# AMR3350-V4.net
KiCad netlist of a schematic drawn in EAGLE
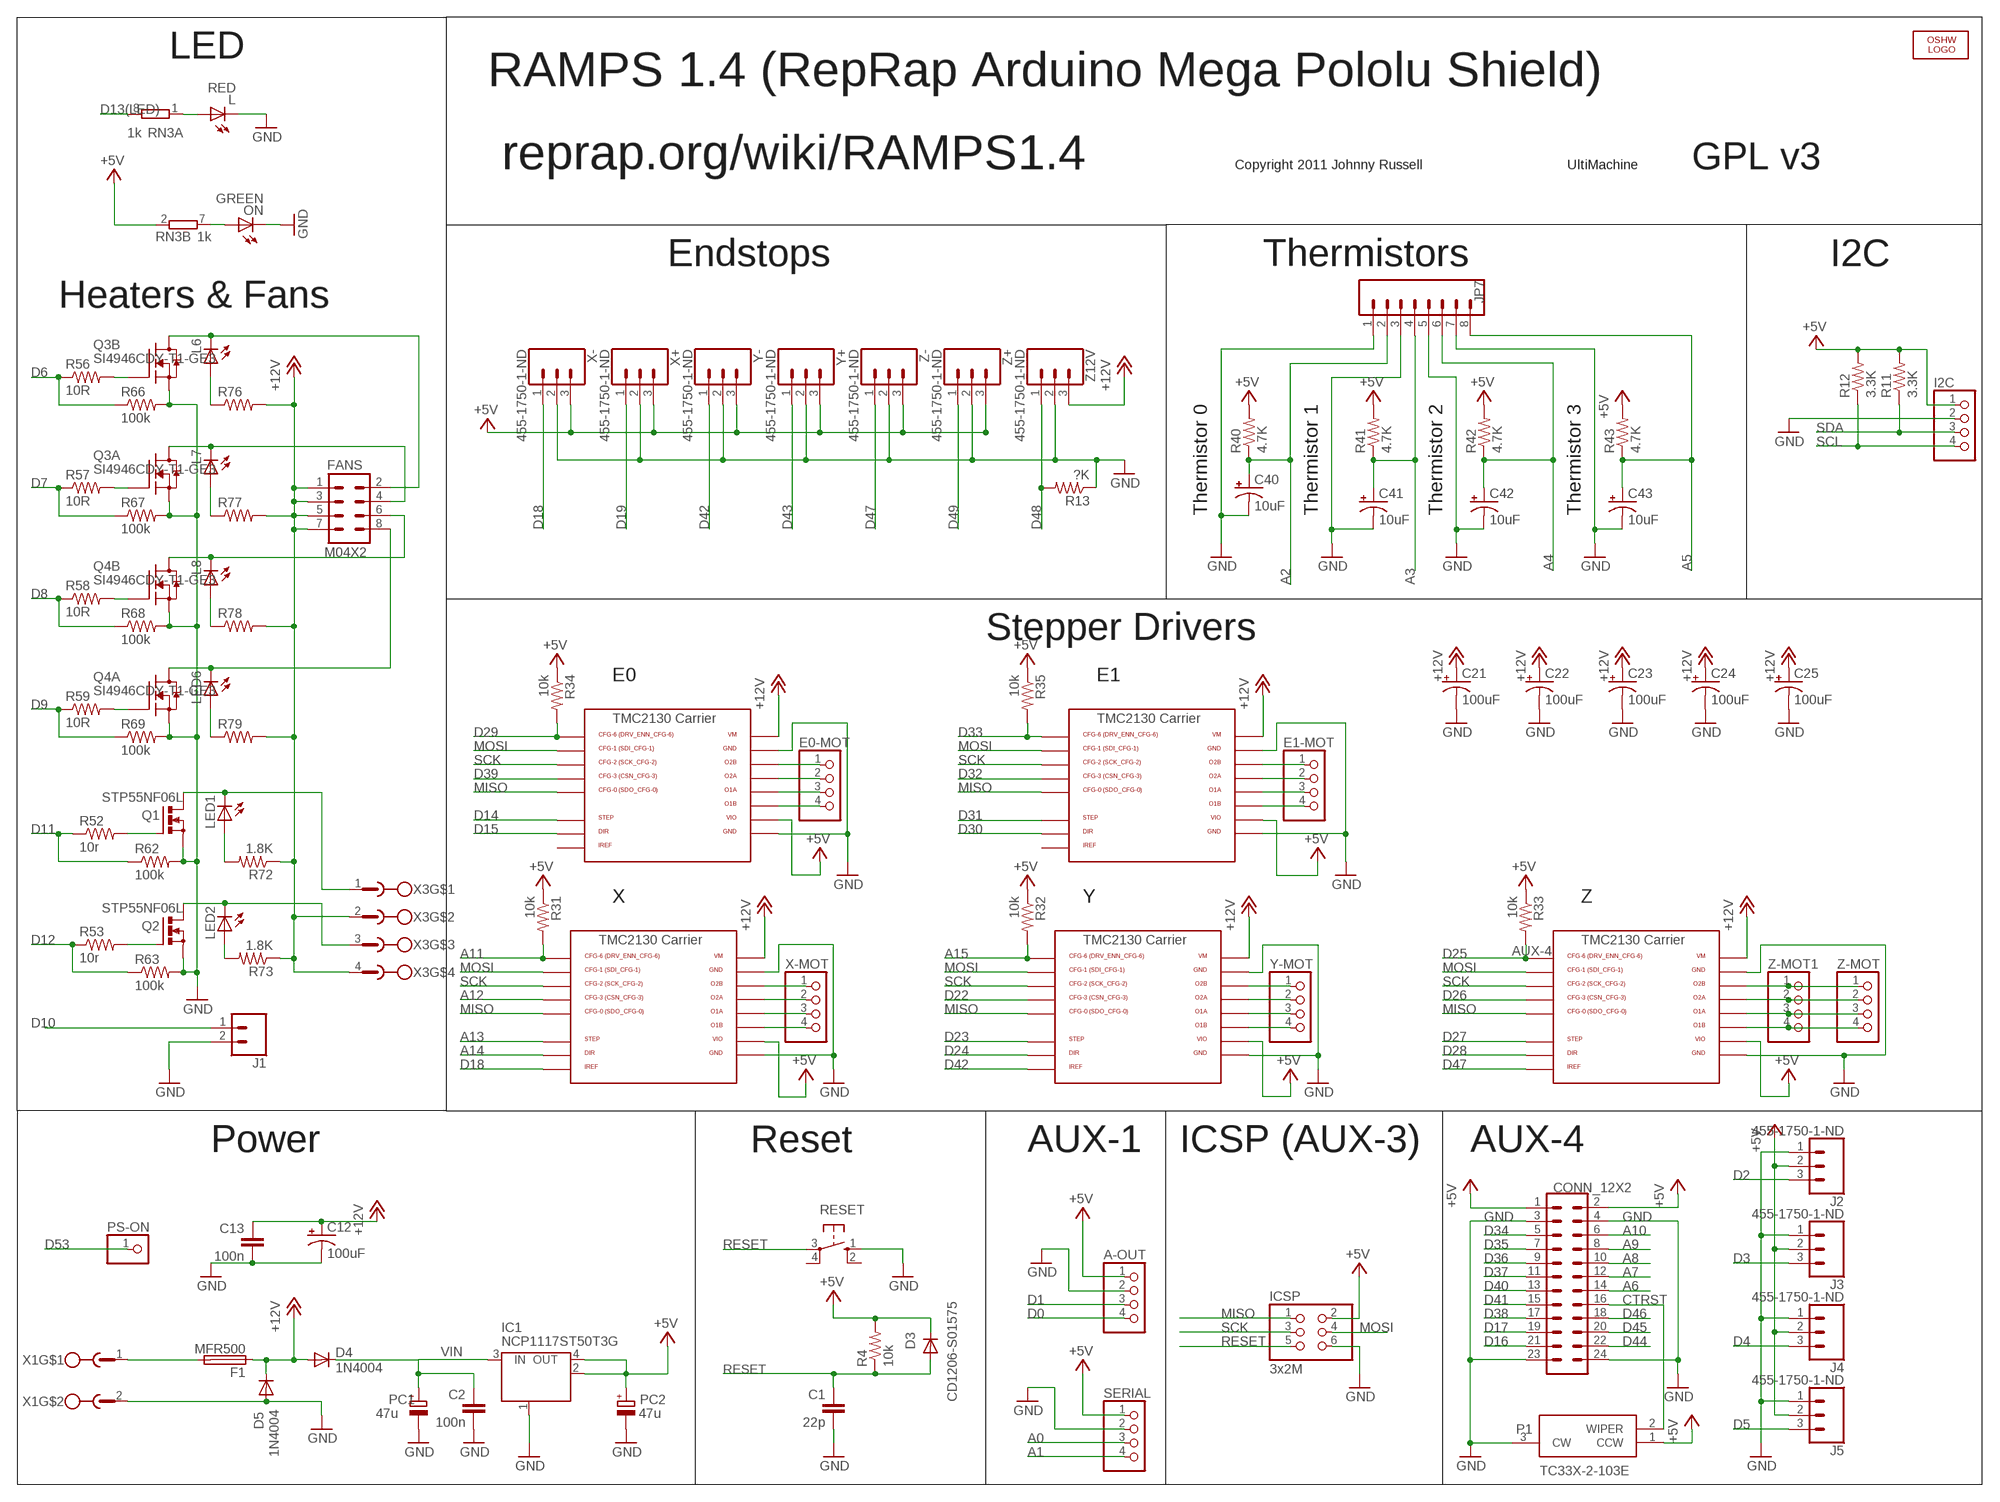
[diagram p0: schematic, sheet 1, part 1 of 2]
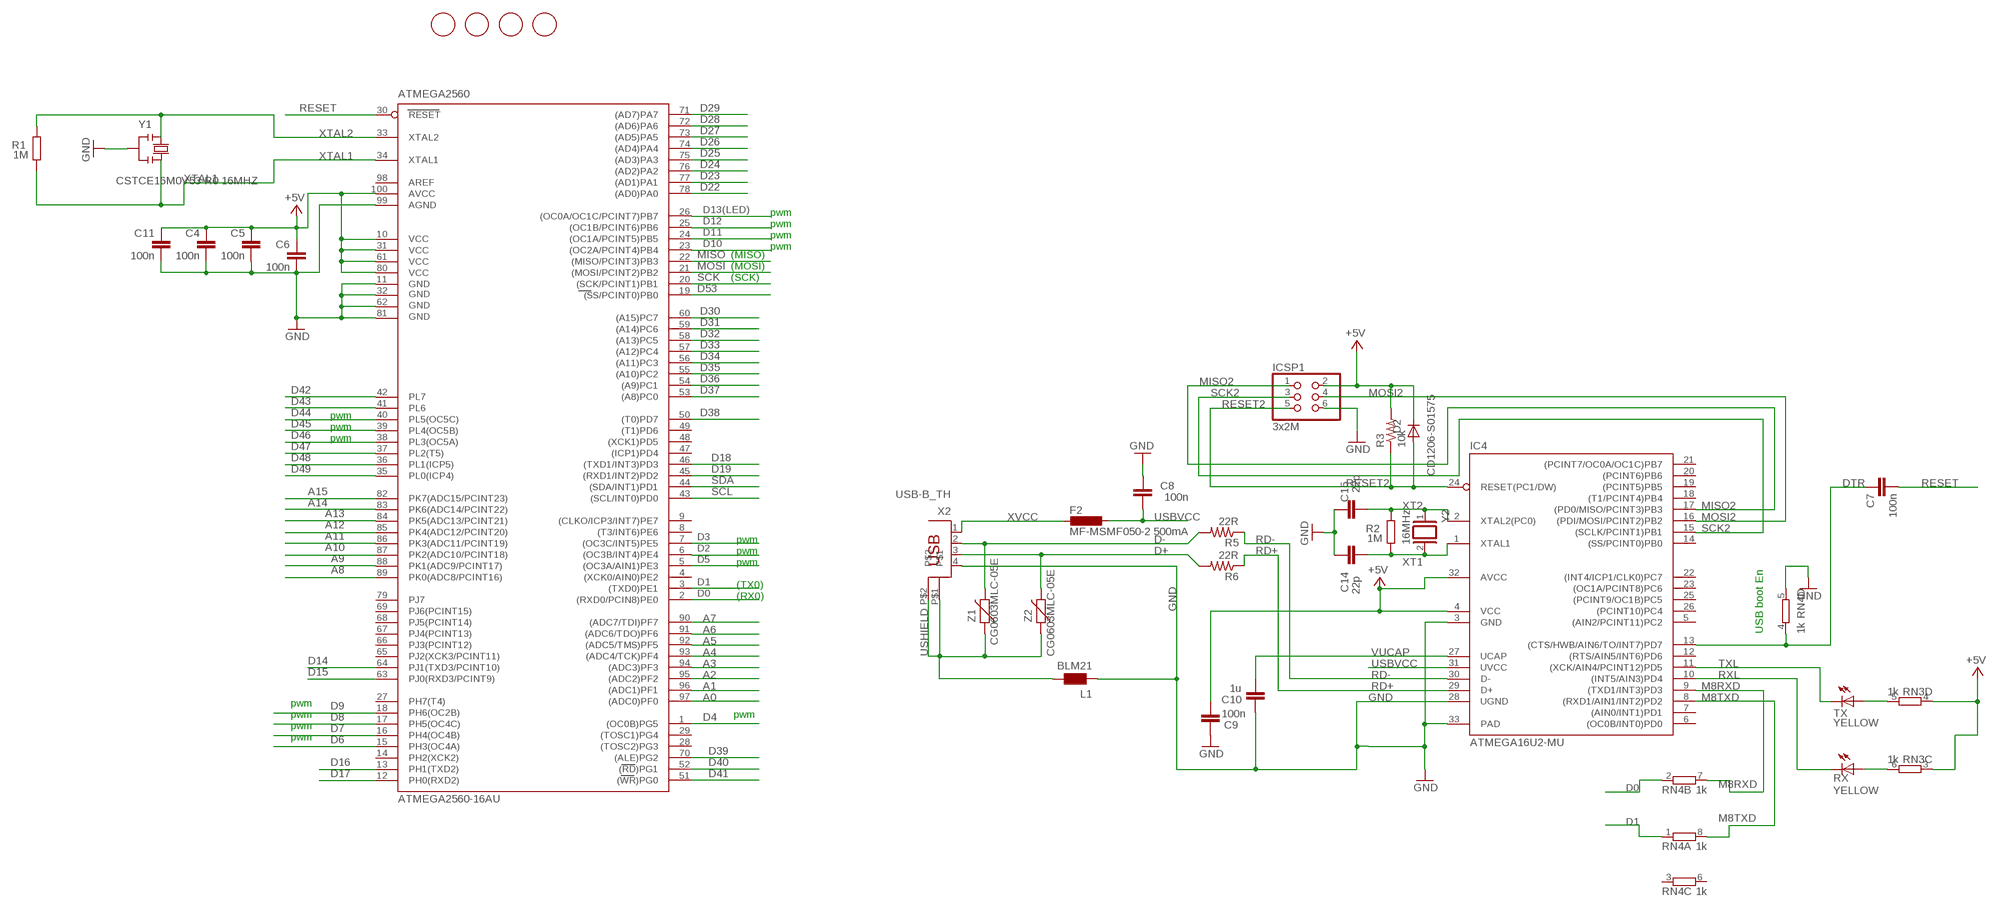
[diagram p1: schematic, sheet 1, part 2 of 2]

(export (version "E")
  (design (tool "Eeschema 10.0.6"))
  (components
    (comp (ref "A-OUT")
      (value "PINHD-1X4")
      (footprint "eagle-import:1X04")
      (libsource (lib "eagle-import") (part "PINHD-1X4"))
    )
    (comp (ref "ATMEGA2560")
      (value "ATMEGA2560-16AU")
      (footprint "eagle-import:TQFP100")
      (libsource (lib "eagle-import") (part "ATMEGA2560AU2560-16"))
    )
    (comp (ref "AUX-4")
      (value "CONN_12X2")
      (footprint "eagle-import:2X12")
      (libsource (lib "eagle-import") (part "CONN_12X2"))
    )
    (comp (ref "C1")
      (value "22p")
      (footprint "eagle-import:C0603-ROUND")
      (libsource (lib "eagle-import") (part "C-EU0603-RND"))
    )
    (comp (ref "C2")
      (value "100n")
      (footprint "eagle-import:C0805RND")
      (libsource (lib "eagle-import") (part "C-EU"))
    )
    (comp (ref "C4")
      (value "100n")
      (footprint "eagle-import:C0805RND")
      (libsource (lib "eagle-import") (part "C-EU"))
    )
    (comp (ref "C5")
      (value "100n")
      (footprint "eagle-import:C0603-ROUND")
      (libsource (lib "eagle-import") (part "C-EU0603-RND"))
    )
    (comp (ref "C6")
      (value "100n")
      (footprint "eagle-import:C0603-ROUND")
      (libsource (lib "eagle-import") (part "C-EU0603-RND"))
    )
    (comp (ref "C7")
      (value "100n")
      (footprint "eagle-import:C0603-ROUND")
      (libsource (lib "eagle-import") (part "C-EU0603-RND"))
    )
    (comp (ref "C8")
      (value "100n")
      (footprint "eagle-import:C0603-ROUND")
      (libsource (lib "eagle-import") (part "C-EU0603-RND"))
    )
    (comp (ref "C9")
      (value "100n")
      (footprint "eagle-import:C0603-ROUND")
      (libsource (lib "eagle-import") (part "C-EU0603-RND"))
    )
    (comp (ref "C10")
      (value "1u")
      (footprint "eagle-import:C0603-ROUND")
      (libsource (lib "eagle-import") (part "C-EU0603-RND"))
    )
    (comp (ref "C11")
      (value "100n")
      (footprint "eagle-import:C0603-ROUND")
      (libsource (lib "eagle-import") (part "C-EU0603-RND"))
    )
    (comp (ref "C12")
      (value "100uF")
      (footprint "eagle-import:153CLV-0605")
      (libsource (lib "eagle-import") (part "CPOL-US153CLV-0605"))
    )
    (comp (ref "C13")
      (value "100n")
      (footprint "eagle-import:C0603-ROUND")
      (libsource (lib "eagle-import") (part "C-EU0603-RND"))
    )
    (comp (ref "C14")
      (value "22p")
      (footprint "eagle-import:C0603-ROUND")
      (libsource (lib "eagle-import") (part "C-EU0603-RND"))
    )
    (comp (ref "C15")
      (value "22p")
      (footprint "eagle-import:C0603-ROUND")
      (libsource (lib "eagle-import") (part "C-EU0603-RND"))
    )
    (comp (ref "C21")
      (value "100uF")
      (footprint "eagle-import:153CLV-0605")
      (libsource (lib "eagle-import") (part "CPOL-US153CLV-0605"))
    )
    (comp (ref "C22")
      (value "100uF")
      (footprint "eagle-import:153CLV-0605")
      (libsource (lib "eagle-import") (part "CPOL-US153CLV-0605"))
    )
    (comp (ref "C23")
      (value "100uF")
      (footprint "eagle-import:153CLV-0605")
      (libsource (lib "eagle-import") (part "CPOL-US153CLV-0605"))
    )
    (comp (ref "C24")
      (value "100uF")
      (footprint "eagle-import:153CLV-0605")
      (libsource (lib "eagle-import") (part "CPOL-US153CLV-0605"))
    )
    (comp (ref "C25")
      (value "100uF")
      (footprint "eagle-import:153CLV-0605")
      (libsource (lib "eagle-import") (part "CPOL-US153CLV-0605"))
    )
    (comp (ref "C40")
      (value "10uF")
      (footprint "eagle-import:153CLV-0405")
      (libsource (lib "eagle-import") (part "CPOL-US153CLV-0405"))
    )
    (comp (ref "C41")
      (value "10uF")
      (footprint "eagle-import:153CLV-0405")
      (libsource (lib "eagle-import") (part "CPOL-US153CLV-0405"))
    )
    (comp (ref "C42")
      (value "10uF")
      (footprint "eagle-import:153CLV-0405")
      (libsource (lib "eagle-import") (part "CPOL-US153CLV-0405"))
    )
    (comp (ref "C43")
      (value "10uF")
      (footprint "eagle-import:153CLV-0405")
      (libsource (lib "eagle-import") (part "CPOL-US153CLV-0405"))
    )
    (comp (ref "D2")
      (value "CD1206-S01575")
      (footprint "eagle-import:MINIMELF")
      (libsource (lib "eagle-import") (part "DIODE-MINIMELF"))
    )
    (comp (ref "D3")
      (value "CD1206-S01575")
      (footprint "eagle-import:MINIMELF")
      (libsource (lib "eagle-import") (part "DIODE-MINIMELF"))
    )
    (comp (ref "D4")
      (value "1N4004")
      (footprint "eagle-import:DO41-10")
      (libsource (lib "eagle-import") (part "1N4004"))
    )
    (comp (ref "D5")
      (value "1N4004")
      (footprint "eagle-import:DO41-10")
      (libsource (lib "eagle-import") (part "1N4004"))
    )
    (comp (ref "E0-MOT")
      (value "PINHD-1X4")
      (footprint "eagle-import:1X04")
      (libsource (lib "eagle-import") (part "PINHD-1X4"))
    )
    (comp (ref "E1-MOT")
      (value "PINHD-1X4")
      (footprint "eagle-import:1X04")
      (libsource (lib "eagle-import") (part "PINHD-1X4"))
    )
    (comp (ref "F1")
      (value "MFR500")
      (footprint "eagle-import:MFR500")
      (libsource (lib "eagle-import") (part "PTCFUSE"))
    )
    (comp (ref "F2")
      (value "MF-MSMF050-2 500mA")
      (footprint "eagle-import:L1812")
      (libsource (lib "eagle-import") (part "L-EUL1812"))
    )
    (comp (ref "FANS")
      (value "M04X2")
      (footprint "eagle-import:2X4")
      (libsource (lib "eagle-import") (part "M04X2"))
    )
    (comp (ref "FD1")
      (value "FIDUCIALMOUNT")
      (footprint "eagle-import:FIDUCIA-MOUNT")
      (libsource (lib "eagle-import") (part "FIDUCIALMOUNT"))
    )
    (comp (ref "FD2")
      (value "FIDUCIALMOUNT")
      (footprint "eagle-import:FIDUCIA-MOUNT")
      (libsource (lib "eagle-import") (part "FIDUCIALMOUNT"))
    )
    (comp (ref "FD3")
      (value "FIDUCIALMOUNT")
      (footprint "eagle-import:FIDUCIA-MOUNT")
      (libsource (lib "eagle-import") (part "FIDUCIALMOUNT"))
    )
    (comp (ref "FD4")
      (value "FIDUCIALMOUNT")
      (footprint "eagle-import:FIDUCIA-MOUNT")
      (libsource (lib "eagle-import") (part "FIDUCIALMOUNT"))
    )
    (comp (ref "I2C")
      (value "PINHD-1X4")
      (footprint "eagle-import:1X04")
      (libsource (lib "eagle-import") (part "PINHD-1X4"))
    )
    (comp (ref "IC1")
      (value "NCP1117ST50T3G")
      (footprint "eagle-import:SOT223")
      (libsource (lib "eagle-import") (part "MC33269ST-3.3T3"))
    )
    (comp (ref "IC4")
      (value "ATMEGA16U2-MU")
      (footprint "eagle-import:MLF32")
      (libsource (lib "eagle-import") (part "ATMEGA16U2-MU"))
    )
    (comp (ref "ICSP")
      (value "3x2M")
      (footprint "eagle-import:2X03")
      (libsource (lib "eagle-import") (part "PINHD-2X3"))
    )
    (comp (ref "ICSP1")
      (value "3x2M")
      (footprint "eagle-import:2X03")
      (libsource (lib "eagle-import") (part "PINHD-2X3"))
    )
    (comp (ref "J1")
      (value "CONN_02")
      (footprint "eagle-import:1X02")
      (libsource (lib "eagle-import") (part "CONN_02"))
    )
    (comp (ref "J2")
      (value "455-1750-1-ND")
      (footprint "eagle-import:1X03")
      (libsource (lib "eagle-import") (part "CONN_03"))
    )
    (comp (ref "J3")
      (value "455-1750-1-ND")
      (footprint "eagle-import:1X03")
      (libsource (lib "eagle-import") (part "CONN_03"))
    )
    (comp (ref "J4")
      (value "455-1750-1-ND")
      (footprint "eagle-import:1X03")
      (libsource (lib "eagle-import") (part "CONN_03"))
    )
    (comp (ref "J5")
      (value "455-1750-1-ND")
      (footprint "eagle-import:1X03")
      (libsource (lib "eagle-import") (part "CONN_03"))
    )
    (comp (ref "JP7")
      (value "CONN_08\"")
      (footprint "eagle-import:1X08")
      (libsource (lib "eagle-import") (part "CONN_08{dblquote}"))
    )
    (comp (ref "L")
      (value "RED")
      (footprint "eagle-import:CHIP-LED0805")
      (libsource (lib "eagle-import") (part "LEDCHIP-LED0805"))
    )
    (comp (ref "L1")
      (value "BLM21")
      (footprint "eagle-import:0805")
      (libsource (lib "eagle-import") (part "WE-CBF_0805"))
    )
    (comp (ref "L6")
      (value "LEDCHIP-LED0603")
      (footprint "eagle-import:CHIP-LED0603")
      (libsource (lib "eagle-import") (part "LEDCHIP-LED0603"))
    )
    (comp (ref "L7")
      (value "LEDCHIP-LED0603")
      (footprint "eagle-import:CHIP-LED0603")
      (libsource (lib "eagle-import") (part "LEDCHIP-LED0603"))
    )
    (comp (ref "L8")
      (value "LEDCHIP-LED0603")
      (footprint "eagle-import:CHIP-LED0603")
      (libsource (lib "eagle-import") (part "LEDCHIP-LED0603"))
    )
    (comp (ref "LED1")
      (value "LEDCHIP-LED0805")
      (footprint "eagle-import:CHIP-LED0805")
      (libsource (lib "eagle-import") (part "LEDCHIP-LED0805"))
    )
    (comp (ref "LED2")
      (value "LEDCHIP-LED0805")
      (footprint "eagle-import:CHIP-LED0805")
      (libsource (lib "eagle-import") (part "LEDCHIP-LED0805"))
    )
    (comp (ref "LED6")
      (value "LEDCHIP-LED0603")
      (footprint "eagle-import:CHIP-LED0603")
      (libsource (lib "eagle-import") (part "LEDCHIP-LED0603"))
    )
    (comp (ref "LOGO2")
      (value "OSHW_LOGO_6MILX0100-NT")
      (footprint "eagle-import:OSHW_6X100_NOTEXT")
      (libsource (lib "eagle-import") (part "OSHW_LOGO_6MILX0100-NT"))
    )
    (comp (ref "ON")
      (value "GREEN")
      (footprint "eagle-import:CHIP-LED0805")
      (libsource (lib "eagle-import") (part "LEDCHIP-LED0805"))
    )
    (comp (ref "P1")
      (value "TC33X-2-103E")
      (footprint "eagle-import:TC33X-2_1")
      (fields (field (name "RS_PART_NUMBER") "1673549"))
      (libsource (lib "eagle-import") (part "TC33X-2-103E"))
    )
    (comp (ref "PC1")
      (value "47u")
      (footprint "eagle-import:PANASONIC_D")
      (libsource (lib "eagle-import") (part "CPOL-EUD"))
    )
    (comp (ref "PC2")
      (value "47u")
      (footprint "eagle-import:PANASONIC_D")
      (libsource (lib "eagle-import") (part "CPOL-EUD"))
    )
    (comp (ref "PS-ON")
      (value "PINHD-1X1")
      (footprint "eagle-import:1X01")
      (libsource (lib "eagle-import") (part "PINHD-1X1"))
    )
    (comp (ref "Q1")
      (value "STP55NF06L")
      (footprint "eagle-import:TO220BV")
      (libsource (lib "eagle-import") (part "IRF512"))
    )
    (comp (ref "Q2")
      (value "STP55NF06L")
      (footprint "eagle-import:TO220BV")
      (libsource (lib "eagle-import") (part "IRF512"))
    )
    (comp (ref "Q3")
      (value "SI4946CDY-T1-GE3")
      (footprint "eagle-import:SOIC127P600X175-8N")
      (libsource (lib "eagle-import") (part "SI4946CDY-T1-GE3"))
    )
    (comp (ref "Q4")
      (value "SI4946CDY-T1-GE3")
      (footprint "eagle-import:SOIC127P600X175-8N")
      (libsource (lib "eagle-import") (part "SI4946CDY-T1-GE3"))
    )
    (comp (ref "R1")
      (value "1M")
      (footprint "eagle-import:R0603-ROUND")
      (libsource (lib "eagle-import") (part "R-EU_R0603"))
    )
    (comp (ref "R2")
      (value "1M")
      (footprint "eagle-import:R0603-ROUND")
      (libsource (lib "eagle-import") (part "R-EU_R0603"))
    )
    (comp (ref "R3")
      (value "10k")
      (footprint "eagle-import:R0603")
      (libsource (lib "eagle-import") (part "resistor_348_R-US_R0603"))
    )
    (comp (ref "R4")
      (value "10k")
      (footprint "eagle-import:R0603")
      (libsource (lib "eagle-import") (part "resistor_348_R-US_R0603"))
    )
    (comp (ref "R5")
      (value "22R")
      (footprint "eagle-import:R0603")
      (libsource (lib "eagle-import") (part "resistor_348_R-US_R0603"))
    )
    (comp (ref "R6")
      (value "22R")
      (footprint "eagle-import:R0603")
      (libsource (lib "eagle-import") (part "resistor_348_R-US_R0603"))
    )
    (comp (ref "R11")
      (value "3.3K")
      (footprint "eagle-import:R0603")
      (libsource (lib "eagle-import") (part "R-US_R0603"))
    )
    (comp (ref "R12")
      (value "3.3K")
      (footprint "eagle-import:R0603")
      (libsource (lib "eagle-import") (part "R-US_R0603"))
    )
    (comp (ref "R13")
      (value "?K")
      (footprint "eagle-import:R0805")
      (libsource (lib "eagle-import") (part "R-US_R0805"))
    )
    (comp (ref "R31")
      (value "10k")
      (footprint "eagle-import:R0805")
      (libsource (lib "eagle-import") (part "R-US_R0805"))
    )
    (comp (ref "R32")
      (value "10k")
      (footprint "eagle-import:R0805")
      (libsource (lib "eagle-import") (part "R-US_R0805"))
    )
    (comp (ref "R33")
      (value "10k")
      (footprint "eagle-import:R0805")
      (libsource (lib "eagle-import") (part "R-US_R0805"))
    )
    (comp (ref "R34")
      (value "10k")
      (footprint "eagle-import:R0805")
      (libsource (lib "eagle-import") (part "R-US_R0805"))
    )
    (comp (ref "R35")
      (value "10k")
      (footprint "eagle-import:R0805")
      (libsource (lib "eagle-import") (part "R-US_R0805"))
    )
    (comp (ref "R40")
      (value "4.7K")
      (footprint "eagle-import:R0805")
      (libsource (lib "eagle-import") (part "R-US_R0805"))
    )
    (comp (ref "R41")
      (value "4.7K")
      (footprint "eagle-import:R0805")
      (libsource (lib "eagle-import") (part "R-US_R0805"))
    )
    (comp (ref "R42")
      (value "4.7K")
      (footprint "eagle-import:R0805")
      (libsource (lib "eagle-import") (part "R-US_R0805"))
    )
    (comp (ref "R43")
      (value "4.7K")
      (footprint "eagle-import:R0805")
      (libsource (lib "eagle-import") (part "R-US_R0805"))
    )
    (comp (ref "R52")
      (value "10r")
      (footprint "eagle-import:R0805")
      (libsource (lib "eagle-import") (part "resistor_R-US_R0805"))
    )
    (comp (ref "R53")
      (value "10r")
      (footprint "eagle-import:M0805")
      (libsource (lib "eagle-import") (part "resistor_R-US_M0805"))
    )
    (comp (ref "R56")
      (value "10R")
      (footprint "eagle-import:R0603")
      (libsource (lib "eagle-import") (part "resistor_348_R-US_R0603"))
    )
    (comp (ref "R57")
      (value "10R")
      (footprint "eagle-import:R0603")
      (libsource (lib "eagle-import") (part "resistor_348_R-US_R0603"))
    )
    (comp (ref "R58")
      (value "10R")
      (footprint "eagle-import:R0603")
      (libsource (lib "eagle-import") (part "resistor_348_R-US_R0603"))
    )
    (comp (ref "R59")
      (value "10R")
      (footprint "eagle-import:R0603")
      (libsource (lib "eagle-import") (part "resistor_348_R-US_R0603"))
    )
    (comp (ref "R62")
      (value "100k")
      (footprint "eagle-import:R0805")
      (libsource (lib "eagle-import") (part "R-US_R0805"))
    )
    (comp (ref "R63")
      (value "100k")
      (footprint "eagle-import:R0805")
      (libsource (lib "eagle-import") (part "R-US_R0805"))
    )
    (comp (ref "R66")
      (value "100k")
      (footprint "eagle-import:R0603")
      (libsource (lib "eagle-import") (part "resistor_348_R-US_R0603"))
    )
    (comp (ref "R67")
      (value "100k")
      (footprint "eagle-import:R0603")
      (libsource (lib "eagle-import") (part "resistor_348_R-US_R0603"))
    )
    (comp (ref "R68")
      (value "100k")
      (footprint "eagle-import:R0603")
      (libsource (lib "eagle-import") (part "resistor_348_R-US_R0603"))
    )
    (comp (ref "R69")
      (value "100k")
      (footprint "eagle-import:R0603")
      (libsource (lib "eagle-import") (part "resistor_348_R-US_R0603"))
    )
    (comp (ref "R72")
      (value "1.8K")
      (footprint "eagle-import:R0805")
      (libsource (lib "eagle-import") (part "R-US_R0805"))
    )
    (comp (ref "R73")
      (value "1.8K")
      (footprint "eagle-import:R0805")
      (libsource (lib "eagle-import") (part "R-US_R0805"))
    )
    (comp (ref "R76")
      (value "R-US_R0603")
      (footprint "eagle-import:R0603")
      (libsource (lib "eagle-import") (part "resistor_348_R-US_R0603"))
    )
    (comp (ref "R77")
      (value "R-US_R0603")
      (footprint "eagle-import:R0603")
      (libsource (lib "eagle-import") (part "resistor_348_R-US_R0603"))
    )
    (comp (ref "R78")
      (value "R-US_R0603")
      (footprint "eagle-import:R0603")
      (libsource (lib "eagle-import") (part "resistor_348_R-US_R0603"))
    )
    (comp (ref "R79")
      (value "R-US_R0603")
      (footprint "eagle-import:R0603")
      (libsource (lib "eagle-import") (part "resistor_348_R-US_R0603"))
    )
    (comp (ref "RESET")
      (value "10-XX")
      (footprint "eagle-import:B3F-10XX")
      (fields (field (name "MPN") "B3F-1000"))
      (libsource (lib "eagle-import") (part "10-XX"))
    )
    (comp (ref "RN3")
      (value "1k")
      (footprint "eagle-import:CAY16")
      (libsource (lib "eagle-import") (part "4R-NCAY16"))
    )
    (comp (ref "RN4")
      (value "1k")
      (footprint "eagle-import:CAY16")
      (libsource (lib "eagle-import") (part "4R-NCAY16"))
    )
    (comp (ref "RX")
      (value "YELLOW")
      (footprint "eagle-import:CHIP-LED0805")
      (libsource (lib "eagle-import") (part "LEDCHIP-LED0805"))
    )
    (comp (ref "SERIAL")
      (value "PINHD-1X4")
      (footprint "eagle-import:1X04")
      (libsource (lib "eagle-import") (part "PINHD-1X4"))
    )
    (comp (ref "TX")
      (value "YELLOW")
      (footprint "eagle-import:CHIP-LED0805")
      (libsource (lib "eagle-import") (part "LEDCHIP-LED0805"))
    )
    (comp (ref "U$1")
      (value "TMC2130BREAKOUT")
      (footprint "eagle-import:TMC2130BREAKOUT")
      (libsource (lib "eagle-import") (part "TMC2130BREAKOUT"))
    )
    (comp (ref "U$2")
      (value "TMC2130BREAKOUT")
      (footprint "eagle-import:TMC2130BREAKOUT")
      (libsource (lib "eagle-import") (part "TMC2130BREAKOUT"))
    )
    (comp (ref "U$3")
      (value "TMC2130BREAKOUT")
      (footprint "eagle-import:TMC2130BREAKOUT")
      (libsource (lib "eagle-import") (part "TMC2130BREAKOUT"))
    )
    (comp (ref "U$4")
      (value "TMC2130BREAKOUT")
      (footprint "eagle-import:TMC2130BREAKOUT")
      (libsource (lib "eagle-import") (part "TMC2130BREAKOUT"))
    )
    (comp (ref "U$5")
      (value "TMC2130BREAKOUT")
      (footprint "eagle-import:TMC2130BREAKOUT")
      (libsource (lib "eagle-import") (part "TMC2130BREAKOUT"))
    )
    (comp (ref "X+")
      (value "455-1750-1-ND")
      (footprint "eagle-import:1X03")
      (libsource (lib "eagle-import") (part "CONN_03"))
    )
    (comp (ref "X-")
      (value "455-1750-1-ND")
      (footprint "eagle-import:1X03")
      (libsource (lib "eagle-import") (part "CONN_03"))
    )
    (comp (ref "X-MOT")
      (value "PINHD-1X4")
      (footprint "eagle-import:1X04")
      (libsource (lib "eagle-import") (part "PINHD-1X4"))
    )
    (comp (ref "X1")
      (value "2-PIN")
      (footprint "eagle-import:2-PIN")
      (libsource (lib "eagle-import") (part "2-PIN"))
    )
    (comp (ref "X2")
      (value "USB-B_TH")
      (footprint "eagle-import:PN61729-NOSILK")
      (libsource (lib "eagle-import") (part "PN61729NOSILK"))
    )
    (comp (ref "X3")
      (value "4-PIN")
      (footprint "eagle-import:4-PIN")
      (libsource (lib "eagle-import") (part "4-PIN"))
    )
    (comp (ref "Y+")
      (value "455-1750-1-ND")
      (footprint "eagle-import:1X03")
      (libsource (lib "eagle-import") (part "CONN_03"))
    )
    (comp (ref "Y-")
      (value "455-1750-1-ND")
      (footprint "eagle-import:1X03")
      (libsource (lib "eagle-import") (part "CONN_03"))
    )
    (comp (ref "Y-MOT")
      (value "PINHD-1X4")
      (footprint "eagle-import:1X04")
      (libsource (lib "eagle-import") (part "PINHD-1X4"))
    )
    (comp (ref "Y1")
      (value "CSTCE16M0V53-R0 16MHZ")
      (footprint "eagle-import:RESONATOR")
      (libsource (lib "eagle-import") (part "RESONATORMU"))
    )
    (comp (ref "Y2")
      (value "16MHz")
      (footprint "eagle-import:QS")
      (libsource (lib "eagle-import") (part "XTAL/S"))
    )
    (comp (ref "Z+")
      (value "455-1750-1-ND")
      (footprint "eagle-import:1X03")
      (libsource (lib "eagle-import") (part "CONN_03"))
    )
    (comp (ref "Z-")
      (value "455-1750-1-ND")
      (footprint "eagle-import:1X03")
      (libsource (lib "eagle-import") (part "CONN_03"))
    )
    (comp (ref "Z-MOT")
      (value "PINHD-1X4")
      (footprint "eagle-import:1X04")
      (libsource (lib "eagle-import") (part "PINHD-1X4"))
    )
    (comp (ref "Z-MOT1")
      (value "PINHD-1X4")
      (footprint "eagle-import:1X04")
      (libsource (lib "eagle-import") (part "PINHD-1X4"))
    )
    (comp (ref "Z1")
      (value "CG0603MLC-05E")
      (footprint "eagle-import:CT_CN0603")
      (libsource (lib "eagle-import") (part "VARISTORCN0603"))
    )
    (comp (ref "Z2")
      (value "CG0603MLC-05E")
      (footprint "eagle-import:CT_CN0603")
      (libsource (lib "eagle-import") (part "VARISTORCN0603"))
    )
    (comp (ref "Z12V")
      (value "455-1750-1-ND")
      (footprint "eagle-import:1X03")
      (libsource (lib "eagle-import") (part "CONN_03"))
    )
  )
  (nets
    (net (code "1") (name "+5V") (class "Default")
      (node (ref "A-OUT") (pin "1") (pinfunction "1_1") (pintype "passive"))
      (node (ref "ATMEGA2560") (pin "10") (pinfunction "VCC_10") (pintype "power_in"))
      (node (ref "ATMEGA2560") (pin "100") (pinfunction "AVCC_100") (pintype "power_in"))
      (node (ref "ATMEGA2560") (pin "31") (pinfunction "VCC1_31") (pintype "power_in"))
      (node (ref "ATMEGA2560") (pin "61") (pinfunction "VCC2_61") (pintype "power_in"))
      (node (ref "ATMEGA2560") (pin "80") (pinfunction "VCC3_80") (pintype "power_in"))
      (node (ref "AUX-4") (pin "1") (pinfunction "1_1") (pintype "passive"))
      (node (ref "AUX-4") (pin "2") (pinfunction "2_2") (pintype "passive"))
      (node (ref "C11") (pin "1") (pinfunction "1_1") (pintype "passive"))
      (node (ref "C4") (pin "1") (pinfunction "1_1") (pintype "passive"))
      (node (ref "C5") (pin "1") (pinfunction "1_1") (pintype "passive"))
      (node (ref "C6") (pin "1") (pinfunction "1_1") (pintype "passive"))
      (node (ref "C9") (pin "1") (pinfunction "1_1") (pintype "passive"))
      (node (ref "D2") (pin "C") (pinfunction "C_C") (pintype "passive"))
      (node (ref "D3") (pin "C") (pinfunction "C_C") (pintype "passive"))
      (node (ref "I2C") (pin "1") (pinfunction "1_1") (pintype "passive"))
      (node (ref "IC1") (pin "2") (pinfunction "OUT_2") (pintype "passive"))
      (node (ref "IC1") (pin "4") (pinfunction "OUT_4") (pintype "passive"))
      (node (ref "IC4") (pin "32") (pinfunction "AVCC_32") (pintype "power_in"))
      (node (ref "IC4") (pin "4") (pinfunction "VCC_4") (pintype "power_in"))
      (node (ref "ICSP") (pin "2") (pinfunction "2_2") (pintype "passive"))
      (node (ref "ICSP1") (pin "2") (pinfunction "2_2") (pintype "passive"))
      (node (ref "J2") (pin "2") (pinfunction "2_2") (pintype "passive"))
      (node (ref "J3") (pin "2") (pinfunction "2_2") (pintype "passive"))
      (node (ref "J4") (pin "2") (pinfunction "2_2") (pintype "passive"))
      (node (ref "J5") (pin "2") (pinfunction "2_2") (pintype "passive"))
      (node (ref "P1") (pin "1") (pinfunction "CCW_1") (pintype "bidirectional"))
      (node (ref "PC2") (pin "+") (pinfunction "+_+") (pintype "passive"))
      (node (ref "R11") (pin "2") (pinfunction "2_2") (pintype "passive"))
      (node (ref "R12") (pin "2") (pinfunction "2_2") (pintype "passive"))
      (node (ref "R3") (pin "2") (pinfunction "2_2") (pintype "passive"))
      (node (ref "R31") (pin "1") (pinfunction "1_1") (pintype "passive"))
      (node (ref "R32") (pin "1") (pinfunction "1_1") (pintype "passive"))
      (node (ref "R33") (pin "1") (pinfunction "1_1") (pintype "passive"))
      (node (ref "R34") (pin "1") (pinfunction "1_1") (pintype "passive"))
      (node (ref "R35") (pin "1") (pinfunction "1_1") (pintype "passive"))
      (node (ref "R4") (pin "2") (pinfunction "2_2") (pintype "passive"))
      (node (ref "R40") (pin "2") (pinfunction "2_2") (pintype "passive"))
      (node (ref "R41") (pin "2") (pinfunction "2_2") (pintype "passive"))
      (node (ref "R42") (pin "2") (pinfunction "2_2") (pintype "passive"))
      (node (ref "R43") (pin "2") (pinfunction "2_2") (pintype "passive"))
      (node (ref "RN3") (pin "2") (pinfunction "1_2") (pintype "passive"))
      (node (ref "RN3") (pin "3") (pinfunction "1_3") (pintype "passive"))
      (node (ref "RN3") (pin "4") (pinfunction "1_4") (pintype "passive"))
      (node (ref "SERIAL") (pin "1") (pinfunction "1_1") (pintype "passive"))
      (node (ref "U$1") (pin "VIO") (pinfunction "VIO_VIO") (pintype "power_in"))
      (node (ref "U$2") (pin "VIO") (pinfunction "VIO_VIO") (pintype "power_in"))
      (node (ref "U$3") (pin "VIO") (pinfunction "VIO_VIO") (pintype "power_in"))
      (node (ref "U$4") (pin "VIO") (pinfunction "VIO_VIO") (pintype "power_in"))
      (node (ref "U$5") (pin "VIO") (pinfunction "VIO_VIO") (pintype "power_in"))
      (node (ref "X+") (pin "3") (pinfunction "3_3") (pintype "passive"))
      (node (ref "X-") (pin "3") (pinfunction "3_3") (pintype "passive"))
      (node (ref "Y+") (pin "3") (pinfunction "3_3") (pintype "passive"))
      (node (ref "Y-") (pin "3") (pinfunction "3_3") (pintype "passive"))
      (node (ref "Z+") (pin "3") (pinfunction "3_3") (pintype "passive"))
      (node (ref "Z-") (pin "3") (pinfunction "3_3") (pintype "passive"))
    )
    (net (code "2") (name "+12V") (class "Default")
      (node (ref "C12") (pin "+") (pinfunction "+_+") (pintype "passive"))
      (node (ref "C13") (pin "1") (pinfunction "1_1") (pintype "passive"))
      (node (ref "C21") (pin "+") (pinfunction "+_+") (pintype "passive"))
      (node (ref "C22") (pin "+") (pinfunction "+_+") (pintype "passive"))
      (node (ref "C23") (pin "+") (pinfunction "+_+") (pintype "passive"))
      (node (ref "C24") (pin "+") (pinfunction "+_+") (pintype "passive"))
      (node (ref "C25") (pin "+") (pinfunction "+_+") (pintype "passive"))
      (node (ref "D4") (pin "A") (pinfunction "A_A") (pintype "passive"))
      (node (ref "D5") (pin "C") (pinfunction "C_C") (pintype "passive"))
      (node (ref "F1") (pin "1") (pinfunction "1_1") (pintype "passive"))
      (node (ref "FANS") (pin "1") (pinfunction "1_1") (pintype "passive"))
      (node (ref "FANS") (pin "3") (pinfunction "3_3") (pintype "passive"))
      (node (ref "FANS") (pin "5") (pinfunction "5_5") (pintype "passive"))
      (node (ref "FANS") (pin "7") (pinfunction "7_7") (pintype "passive"))
      (node (ref "R72") (pin "1") (pinfunction "1_1") (pintype "passive"))
      (node (ref "R73") (pin "1") (pinfunction "1_1") (pintype "passive"))
      (node (ref "R76") (pin "2") (pinfunction "2_2") (pintype "passive"))
      (node (ref "R77") (pin "2") (pinfunction "2_2") (pintype "passive"))
      (node (ref "R78") (pin "2") (pinfunction "2_2") (pintype "passive"))
      (node (ref "R79") (pin "2") (pinfunction "2_2") (pintype "passive"))
      (node (ref "U$1") (pin "VM") (pinfunction "VM_VM") (pintype "power_in"))
      (node (ref "U$2") (pin "VM") (pinfunction "VM_VM") (pintype "power_in"))
      (node (ref "U$3") (pin "VM") (pinfunction "VM_VM") (pintype "power_in"))
      (node (ref "U$4") (pin "VM") (pinfunction "VM_VM") (pintype "power_in"))
      (node (ref "U$5") (pin "VM") (pinfunction "VM_VM") (pintype "power_in"))
      (node (ref "X3") (pin "2") (pinfunction "1_2") (pintype "passive"))
      (node (ref "X3") (pin "4") (pinfunction "1_4") (pintype "passive"))
      (node (ref "Z12V") (pin "3") (pinfunction "3_3") (pintype "passive"))
    )
    (net (code "3") (name "/A0") (class "Default")
      (node (ref "ATMEGA2560") (pin "97") (pinfunction "(ADC0)PF0_97") (pintype "bidirectional"))
      (node (ref "SERIAL") (pin "3") (pinfunction "3_3") (pintype "passive"))
    )
    (net (code "4") (name "/A1") (class "Default")
      (node (ref "ATMEGA2560") (pin "96") (pinfunction "(ADC1)PF1_96") (pintype "bidirectional"))
      (node (ref "SERIAL") (pin "4") (pinfunction "4_4") (pintype "passive"))
    )
    (net (code "5") (name "/A2") (class "Default")
      (node (ref "ATMEGA2560") (pin "95") (pinfunction "(ADC2)PF2_95") (pintype "bidirectional"))
      (node (ref "C40") (pin "+") (pinfunction "+_+") (pintype "passive"))
      (node (ref "JP7") (pin "2") (pinfunction "2_2") (pintype "passive"))
      (node (ref "R40") (pin "1") (pinfunction "1_1") (pintype "passive"))
    )
    (net (code "6") (name "/A3") (class "Default")
      (node (ref "ATMEGA2560") (pin "94") (pinfunction "(ADC3)PF3_94") (pintype "bidirectional"))
      (node (ref "C41") (pin "+") (pinfunction "+_+") (pintype "passive"))
      (node (ref "JP7") (pin "4") (pinfunction "4_4") (pintype "passive"))
      (node (ref "R41") (pin "1") (pinfunction "1_1") (pintype "passive"))
    )
    (net (code "7") (name "/A4") (class "Default")
      (node (ref "ATMEGA2560") (pin "93") (pinfunction "(ADC4/TCK)PF4_93") (pintype "bidirectional"))
      (node (ref "C42") (pin "+") (pinfunction "+_+") (pintype "passive"))
      (node (ref "JP7") (pin "6") (pinfunction "6_6") (pintype "passive"))
      (node (ref "R42") (pin "1") (pinfunction "1_1") (pintype "passive"))
    )
    (net (code "8") (name "/A5") (class "Default")
      (node (ref "ATMEGA2560") (pin "92") (pinfunction "(ADC5/TMS)PF5_92") (pintype "bidirectional"))
      (node (ref "C43") (pin "+") (pinfunction "+_+") (pintype "passive"))
      (node (ref "JP7") (pin "8") (pinfunction "8_8") (pintype "passive"))
      (node (ref "R43") (pin "1") (pinfunction "1_1") (pintype "passive"))
    )
    (net (code "9") (name "/A6") (class "Default")
      (node (ref "ATMEGA2560") (pin "91") (pinfunction "(ADC6/TDO)PF6_91") (pintype "bidirectional"))
      (node (ref "AUX-4") (pin "14") (pinfunction "14_14") (pintype "passive"))
    )
    (net (code "10") (name "/A7") (class "Default")
      (node (ref "ATMEGA2560") (pin "90") (pinfunction "(ADC7/TDI)PF7_90") (pintype "bidirectional"))
      (node (ref "AUX-4") (pin "12") (pinfunction "12_12") (pintype "passive"))
    )
    (net (code "11") (name "/A8") (class "Default")
      (node (ref "ATMEGA2560") (pin "89") (pinfunction "PK0(ADC8/PCINT16)_89") (pintype "bidirectional"))
      (node (ref "AUX-4") (pin "10") (pinfunction "10_10") (pintype "passive"))
    )
    (net (code "12") (name "/A9") (class "Default")
      (node (ref "ATMEGA2560") (pin "88") (pinfunction "PK1(ADC9/PCINT17)_88") (pintype "bidirectional"))
      (node (ref "AUX-4") (pin "8") (pinfunction "8_8") (pintype "passive"))
    )
    (net (code "13") (name "/A10") (class "Default")
      (node (ref "ATMEGA2560") (pin "87") (pinfunction "PK2(ADC10/PCINT18)_87") (pintype "bidirectional"))
      (node (ref "AUX-4") (pin "6") (pinfunction "6_6") (pintype "passive"))
    )
    (net (code "14") (name "/A11") (class "Default")
      (node (ref "ATMEGA2560") (pin "86") (pinfunction "PK3(ADC11/PCINT19)_86") (pintype "bidirectional"))
      (node (ref "R31") (pin "2") (pinfunction "2_2") (pintype "passive"))
      (node (ref "U$1") (pin "CFG-6") (pinfunction "CFG-6_CFG-6") (pintype "bidirectional"))
    )
    (net (code "15") (name "/A12") (class "Default")
      (node (ref "ATMEGA2560") (pin "85") (pinfunction "PK4(ADC12/PCINT20)_85") (pintype "bidirectional"))
      (node (ref "U$1") (pin "CFG-3") (pinfunction "CFG-3_CFG-3") (pintype "bidirectional"))
    )
    (net (code "16") (name "/A13") (class "Default")
      (node (ref "ATMEGA2560") (pin "84") (pinfunction "PK5(ADC13/PCINT21)_84") (pintype "bidirectional"))
      (node (ref "U$1") (pin "STEP") (pinfunction "STEP_STEP") (pintype "input"))
    )
    (net (code "17") (name "/A14") (class "Default")
      (node (ref "ATMEGA2560") (pin "83") (pinfunction "PK6(ADC14/PCINT22)_83") (pintype "bidirectional"))
      (node (ref "U$1") (pin "DIR") (pinfunction "DIR_DIR") (pintype "input"))
    )
    (net (code "18") (name "/A15") (class "Default")
      (node (ref "ATMEGA2560") (pin "82") (pinfunction "PK7(ADC15/PCINT23)_82") (pintype "bidirectional"))
      (node (ref "R32") (pin "2") (pinfunction "2_2") (pintype "passive"))
      (node (ref "U$2") (pin "CFG-6") (pinfunction "CFG-6_CFG-6") (pintype "bidirectional"))
    )
    (net (code "19") (name "/CTRST") (class "Default")
      (node (ref "AUX-4") (pin "16") (pinfunction "16_16") (pintype "passive"))
      (node (ref "P1") (pin "2") (pinfunction "WIPER_2") (pintype "bidirectional"))
    )
    (net (code "20") (name "/D+") (class "Default")
      (node (ref "R6") (pin "2") (pinfunction "2_2") (pintype "passive"))
      (node (ref "X2") (pin "3") (pinfunction "3_3") (pintype "bidirectional"))
      (node (ref "Z2") (pin "2") (pinfunction "2_2") (pintype "passive"))
    )
    (net (code "21") (name "/D-") (class "Default")
      (node (ref "R5") (pin "2") (pinfunction "2_2") (pintype "passive"))
      (node (ref "X2") (pin "2") (pinfunction "2_2") (pintype "bidirectional"))
      (node (ref "Z1") (pin "2") (pinfunction "2_2") (pintype "passive"))
    )
    (net (code "22") (name "/D0") (class "Default")
      (node (ref "A-OUT") (pin "4") (pinfunction "4_4") (pintype "passive"))
      (node (ref "ATMEGA2560") (pin "2") (pinfunction "(RXD0/PCIN8)PE0_2") (pintype "bidirectional"))
      (node (ref "RN4") (pin "2") (pinfunction "1_2") (pintype "passive"))
    )
    (net (code "23") (name "/D1") (class "Default")
      (node (ref "A-OUT") (pin "3") (pinfunction "3_3") (pintype "passive"))
      (node (ref "ATMEGA2560") (pin "3") (pinfunction "(TXD0)PE1_3") (pintype "bidirectional"))
      (node (ref "RN4") (pin "1") (pinfunction "1_1") (pintype "passive"))
    )
    (net (code "24") (name "/D2") (class "Default")
      (node (ref "ATMEGA2560") (pin "6") (pinfunction "(OC3B/INT4)PE4_6") (pintype "bidirectional"))
      (node (ref "J2") (pin "3") (pinfunction "3_3") (pintype "passive"))
    )
    (net (code "25") (name "/D3") (class "Default")
      (node (ref "ATMEGA2560") (pin "7") (pinfunction "(OC3C/INT5)PE5_7") (pintype "bidirectional"))
      (node (ref "J3") (pin "3") (pinfunction "3_3") (pintype "passive"))
    )
    (net (code "26") (name "/D4") (class "Default")
      (node (ref "ATMEGA2560") (pin "1") (pinfunction "(OC0B)PG5_1") (pintype "bidirectional"))
      (node (ref "J4") (pin "3") (pinfunction "3_3") (pintype "passive"))
    )
    (net (code "27") (name "/D5") (class "Default")
      (node (ref "ATMEGA2560") (pin "5") (pinfunction "(OC3A/AIN1)PE3_5") (pintype "bidirectional"))
      (node (ref "J5") (pin "3") (pinfunction "3_3") (pintype "passive"))
    )
    (net (code "28") (name "/D6") (class "Default")
      (node (ref "ATMEGA2560") (pin "15") (pinfunction "PH3(OC4A)_15") (pintype "bidirectional"))
      (node (ref "R56") (pin "1") (pinfunction "1_1") (pintype "passive"))
      (node (ref "R66") (pin "1") (pinfunction "1_1") (pintype "passive"))
    )
    (net (code "29") (name "/D7") (class "Default")
      (node (ref "ATMEGA2560") (pin "16") (pinfunction "PH4(OC4B)_16") (pintype "bidirectional"))
      (node (ref "R57") (pin "1") (pinfunction "1_1") (pintype "passive"))
      (node (ref "R67") (pin "1") (pinfunction "1_1") (pintype "passive"))
    )
    (net (code "30") (name "/D8") (class "Default")
      (node (ref "ATMEGA2560") (pin "17") (pinfunction "PH5(OC4C)_17") (pintype "bidirectional"))
      (node (ref "R58") (pin "1") (pinfunction "1_1") (pintype "passive"))
      (node (ref "R68") (pin "1") (pinfunction "1_1") (pintype "passive"))
    )
    (net (code "31") (name "/D9") (class "Default")
      (node (ref "ATMEGA2560") (pin "18") (pinfunction "PH6(OC2B)_18") (pintype "bidirectional"))
      (node (ref "R59") (pin "1") (pinfunction "1_1") (pintype "passive"))
      (node (ref "R69") (pin "1") (pinfunction "1_1") (pintype "passive"))
    )
    (net (code "32") (name "/D10") (class "Default")
      (node (ref "ATMEGA2560") (pin "23") (pinfunction "(OC2A/PCINT4)PB4_23") (pintype "bidirectional"))
      (node (ref "J1") (pin "1") (pinfunction "1_1") (pintype "passive"))
    )
    (net (code "33") (name "/D11") (class "Default")
      (node (ref "ATMEGA2560") (pin "24") (pinfunction "(OC1A/PCINT5)PB5_24") (pintype "bidirectional"))
      (node (ref "R52") (pin "1") (pinfunction "1_1") (pintype "passive"))
      (node (ref "R62") (pin "1") (pinfunction "1_1") (pintype "passive"))
    )
    (net (code "34") (name "/D12") (class "Default")
      (node (ref "ATMEGA2560") (pin "25") (pinfunction "(OC1B/PCINT6)PB6_25") (pintype "bidirectional"))
      (node (ref "R53") (pin "1") (pinfunction "1_1") (pintype "passive"))
      (node (ref "R63") (pin "1") (pinfunction "1_1") (pintype "passive"))
    )
    (net (code "35") (name "/D13(LED)") (class "Default")
      (node (ref "ATMEGA2560") (pin "26") (pinfunction "(OC0A/OC1C/PCINT7)PB7_26") (pintype "bidirectional"))
      (node (ref "RN3") (pin "8") (pinfunction "2_8") (pintype "passive"))
    )
    (net (code "36") (name "/D14") (class "Default")
      (node (ref "ATMEGA2560") (pin "64") (pinfunction "PJ1(TXD3/PCINT10)_64") (pintype "bidirectional"))
      (node (ref "U$5") (pin "STEP") (pinfunction "STEP_STEP") (pintype "input"))
    )
    (net (code "37") (name "/D15") (class "Default")
      (node (ref "ATMEGA2560") (pin "63") (pinfunction "PJ0(RXD3/PCINT9)_63") (pintype "bidirectional"))
      (node (ref "U$5") (pin "DIR") (pinfunction "DIR_DIR") (pintype "input"))
    )
    (net (code "38") (name "/D16") (class "Default")
      (node (ref "ATMEGA2560") (pin "13") (pinfunction "PH1(TXD2)_13") (pintype "bidirectional"))
      (node (ref "AUX-4") (pin "21") (pinfunction "21_21") (pintype "passive"))
    )
    (net (code "39") (name "/D17") (class "Default")
      (node (ref "ATMEGA2560") (pin "12") (pinfunction "PH0(RXD2)_12") (pintype "bidirectional"))
      (node (ref "AUX-4") (pin "19") (pinfunction "19_19") (pintype "passive"))
    )
    (net (code "40") (name "/D18") (class "Default")
      (node (ref "ATMEGA2560") (pin "46") (pinfunction "(TXD1/INT3)PD3_46") (pintype "bidirectional"))
      (node (ref "U$1") (pin "IREF") (pinfunction "IREF_IREF") (pintype "bidirectional"))
      (node (ref "X-") (pin "1") (pinfunction "1_1") (pintype "passive"))
    )
    (net (code "41") (name "/D19") (class "Default")
      (node (ref "ATMEGA2560") (pin "45") (pinfunction "(RXD1/INT2)PD2_45") (pintype "bidirectional"))
      (node (ref "X+") (pin "1") (pinfunction "1_1") (pintype "passive"))
    )
    (net (code "42") (name "/D22") (class "Default")
      (node (ref "ATMEGA2560") (pin "78") (pinfunction "(AD0)PA0_78") (pintype "bidirectional"))
      (node (ref "U$2") (pin "CFG-3") (pinfunction "CFG-3_CFG-3") (pintype "bidirectional"))
    )
    (net (code "43") (name "/D23") (class "Default")
      (node (ref "ATMEGA2560") (pin "77") (pinfunction "(AD1)PA1_77") (pintype "bidirectional"))
      (node (ref "U$2") (pin "STEP") (pinfunction "STEP_STEP") (pintype "input"))
    )
    (net (code "44") (name "/D24") (class "Default")
      (node (ref "ATMEGA2560") (pin "76") (pinfunction "(AD2)PA2_76") (pintype "bidirectional"))
      (node (ref "U$2") (pin "DIR") (pinfunction "DIR_DIR") (pintype "input"))
    )
    (net (code "45") (name "/D25") (class "Default")
      (node (ref "ATMEGA2560") (pin "75") (pinfunction "(AD3)PA3_75") (pintype "bidirectional"))
      (node (ref "R33") (pin "2") (pinfunction "2_2") (pintype "passive"))
      (node (ref "U$3") (pin "CFG-6") (pinfunction "CFG-6_CFG-6") (pintype "bidirectional"))
    )
    (net (code "46") (name "/D26") (class "Default")
      (node (ref "ATMEGA2560") (pin "74") (pinfunction "(AD4)PA4_74") (pintype "bidirectional"))
      (node (ref "U$3") (pin "CFG-3") (pinfunction "CFG-3_CFG-3") (pintype "bidirectional"))
    )
    (net (code "47") (name "/D27") (class "Default")
      (node (ref "ATMEGA2560") (pin "73") (pinfunction "(AD5)PA5_73") (pintype "bidirectional"))
      (node (ref "U$3") (pin "STEP") (pinfunction "STEP_STEP") (pintype "input"))
    )
    (net (code "48") (name "/D28") (class "Default")
      (node (ref "ATMEGA2560") (pin "72") (pinfunction "(AD6)PA6_72") (pintype "bidirectional"))
      (node (ref "U$3") (pin "DIR") (pinfunction "DIR_DIR") (pintype "input"))
    )
    (net (code "49") (name "/D29") (class "Default")
      (node (ref "ATMEGA2560") (pin "71") (pinfunction "(AD7)PA7_71") (pintype "bidirectional"))
      (node (ref "R34") (pin "2") (pinfunction "2_2") (pintype "passive"))
      (node (ref "U$5") (pin "CFG-6") (pinfunction "CFG-6_CFG-6") (pintype "bidirectional"))
    )
    (net (code "50") (name "/D30") (class "Default")
      (node (ref "ATMEGA2560") (pin "60") (pinfunction "(A15)PC7_60") (pintype "bidirectional"))
      (node (ref "U$4") (pin "DIR") (pinfunction "DIR_DIR") (pintype "input"))
    )
    (net (code "51") (name "/D31") (class "Default")
      (node (ref "ATMEGA2560") (pin "59") (pinfunction "(A14)PC6_59") (pintype "bidirectional"))
      (node (ref "U$4") (pin "STEP") (pinfunction "STEP_STEP") (pintype "input"))
    )
    (net (code "52") (name "/D32") (class "Default")
      (node (ref "ATMEGA2560") (pin "58") (pinfunction "(A13)PC5_58") (pintype "bidirectional"))
      (node (ref "U$4") (pin "CFG-3") (pinfunction "CFG-3_CFG-3") (pintype "bidirectional"))
    )
    (net (code "53") (name "/D33") (class "Default")
      (node (ref "ATMEGA2560") (pin "57") (pinfunction "(A12)PC4_57") (pintype "bidirectional"))
      (node (ref "R35") (pin "2") (pinfunction "2_2") (pintype "passive"))
      (node (ref "U$4") (pin "CFG-6") (pinfunction "CFG-6_CFG-6") (pintype "bidirectional"))
    )
    (net (code "54") (name "/D34") (class "Default")
      (node (ref "ATMEGA2560") (pin "56") (pinfunction "(A11)PC3_56") (pintype "bidirectional"))
      (node (ref "AUX-4") (pin "5") (pinfunction "5_5") (pintype "passive"))
    )
    (net (code "55") (name "/D35") (class "Default")
      (node (ref "ATMEGA2560") (pin "55") (pinfunction "(A10)PC2_55") (pintype "bidirectional"))
      (node (ref "AUX-4") (pin "7") (pinfunction "7_7") (pintype "passive"))
    )
    (net (code "56") (name "/D36") (class "Default")
      (node (ref "ATMEGA2560") (pin "54") (pinfunction "(A9)PC1_54") (pintype "bidirectional"))
      (node (ref "AUX-4") (pin "9") (pinfunction "9_9") (pintype "passive"))
    )
    (net (code "57") (name "/D37") (class "Default")
      (node (ref "ATMEGA2560") (pin "53") (pinfunction "(A8)PC0_53") (pintype "bidirectional"))
      (node (ref "AUX-4") (pin "11") (pinfunction "11_11") (pintype "passive"))
    )
    (net (code "58") (name "/D38") (class "Default")
      (node (ref "ATMEGA2560") (pin "50") (pinfunction "(T0)PD7_50") (pintype "bidirectional"))
      (node (ref "AUX-4") (pin "17") (pinfunction "17_17") (pintype "passive"))
    )
    (net (code "59") (name "/D39") (class "Default")
      (node (ref "ATMEGA2560") (pin "70") (pinfunction "(ALE)PG2_70") (pintype "bidirectional"))
      (node (ref "U$5") (pin "CFG-3") (pinfunction "CFG-3_CFG-3") (pintype "bidirectional"))
    )
    (net (code "60") (name "/D40") (class "Default")
      (node (ref "ATMEGA2560") (pin "52") (pinfunction "(RD)PG1_52") (pintype "bidirectional"))
      (node (ref "AUX-4") (pin "13") (pinfunction "13_13") (pintype "passive"))
    )
    (net (code "61") (name "/D41") (class "Default")
      (node (ref "ATMEGA2560") (pin "51") (pinfunction "(WR)PG0_51") (pintype "bidirectional"))
      (node (ref "AUX-4") (pin "15") (pinfunction "15_15") (pintype "passive"))
    )
    (net (code "62") (name "/D42") (class "Default")
      (node (ref "ATMEGA2560") (pin "42") (pinfunction "PL7_42") (pintype "bidirectional"))
      (node (ref "U$2") (pin "IREF") (pinfunction "IREF_IREF") (pintype "bidirectional"))
      (node (ref "Y-") (pin "1") (pinfunction "1_1") (pintype "passive"))
    )
    (net (code "63") (name "/D43") (class "Default")
      (node (ref "ATMEGA2560") (pin "41") (pinfunction "PL6_41") (pintype "bidirectional"))
      (node (ref "Y+") (pin "1") (pinfunction "1_1") (pintype "passive"))
    )
    (net (code "64") (name "/D44") (class "Default")
      (node (ref "ATMEGA2560") (pin "40") (pinfunction "PL5(OC5C)_40") (pintype "bidirectional"))
      (node (ref "AUX-4") (pin "22") (pinfunction "22_22") (pintype "passive"))
    )
    (net (code "65") (name "/D45") (class "Default")
      (node (ref "ATMEGA2560") (pin "39") (pinfunction "PL4(OC5B)_39") (pintype "bidirectional"))
      (node (ref "AUX-4") (pin "20") (pinfunction "20_20") (pintype "passive"))
    )
    (net (code "66") (name "/D46") (class "Default")
      (node (ref "ATMEGA2560") (pin "38") (pinfunction "PL3(OC5A)_38") (pintype "bidirectional"))
      (node (ref "AUX-4") (pin "18") (pinfunction "18_18") (pintype "passive"))
    )
    (net (code "67") (name "/D47") (class "Default")
      (node (ref "ATMEGA2560") (pin "37") (pinfunction "PL2(T5)_37") (pintype "bidirectional"))
      (node (ref "U$3") (pin "IREF") (pinfunction "IREF_IREF") (pintype "bidirectional"))
      (node (ref "Z-") (pin "1") (pinfunction "1_1") (pintype "passive"))
    )
    (net (code "68") (name "/D48") (class "Default")
      (node (ref "ATMEGA2560") (pin "36") (pinfunction "PL1(ICP5)_36") (pintype "bidirectional"))
      (node (ref "R13") (pin "2") (pinfunction "2_2") (pintype "passive"))
      (node (ref "Z12V") (pin "1") (pinfunction "1_1") (pintype "passive"))
    )
    (net (code "69") (name "/D49") (class "Default")
      (node (ref "ATMEGA2560") (pin "35") (pinfunction "PL0(ICP4)_35") (pintype "bidirectional"))
      (node (ref "Z+") (pin "1") (pinfunction "1_1") (pintype "passive"))
    )
    (net (code "70") (name "/D53") (class "Default")
      (node (ref "ATMEGA2560") (pin "19") (pinfunction "(SS/PCINT0)PB0_19") (pintype "bidirectional"))
      (node (ref "PS-ON") (pin "1") (pinfunction "1_1") (pintype "passive"))
    )
    (net (code "71") (name "/DTR") (class "Default")
      (node (ref "C7") (pin "1") (pinfunction "1_1") (pintype "passive"))
      (node (ref "IC4") (pin "13") (pinfunction "(CTS/HWB/AIN6/TO/INT7)PD7_13") (pintype "bidirectional"))
      (node (ref "RN4") (pin "4") (pinfunction "1_4") (pintype "passive"))
    )
    (net (code "72") (name "/M8RXD") (class "Default")
      (node (ref "IC4") (pin "9") (pinfunction "(TXD1/INT3)PD3_9") (pintype "bidirectional"))
      (node (ref "RN4") (pin "7") (pinfunction "2_7") (pintype "passive"))
    )
    (net (code "73") (name "/M8TXD") (class "Default")
      (node (ref "IC4") (pin "8") (pinfunction "(RXD1/AIN1/INT2)PD2_8") (pintype "bidirectional"))
      (node (ref "RN4") (pin "8") (pinfunction "2_8") (pintype "passive"))
    )
    (net (code "74") (name "/MISO") (class "Default")
      (node (ref "ATMEGA2560") (pin "22") (pinfunction "(MISO/PCINT3)PB3_22") (pintype "bidirectional"))
      (node (ref "ICSP") (pin "1") (pinfunction "1_1") (pintype "passive"))
      (node (ref "U$1") (pin "CFG-0") (pinfunction "CFG-0_CFG-0") (pintype "bidirectional"))
      (node (ref "U$2") (pin "CFG-0") (pinfunction "CFG-0_CFG-0") (pintype "bidirectional"))
      (node (ref "U$3") (pin "CFG-0") (pinfunction "CFG-0_CFG-0") (pintype "bidirectional"))
      (node (ref "U$4") (pin "CFG-0") (pinfunction "CFG-0_CFG-0") (pintype "bidirectional"))
      (node (ref "U$5") (pin "CFG-0") (pinfunction "CFG-0_CFG-0") (pintype "bidirectional"))
    )
    (net (code "75") (name "/MISO2") (class "Default")
      (node (ref "IC4") (pin "17") (pinfunction "(PD0/MISO/PCINT3)PB3_17") (pintype "bidirectional"))
      (node (ref "ICSP1") (pin "1") (pinfunction "1_1") (pintype "passive"))
    )
    (net (code "76") (name "/MOSI") (class "Default")
      (node (ref "ATMEGA2560") (pin "21") (pinfunction "(MOSI/PCINT2)PB2_21") (pintype "bidirectional"))
      (node (ref "ICSP") (pin "4") (pinfunction "4_4") (pintype "passive"))
      (node (ref "U$1") (pin "CFG-1") (pinfunction "CFG-1_CFG-1") (pintype "bidirectional"))
      (node (ref "U$2") (pin "CFG-1") (pinfunction "CFG-1_CFG-1") (pintype "bidirectional"))
      (node (ref "U$3") (pin "CFG-1") (pinfunction "CFG-1_CFG-1") (pintype "bidirectional"))
      (node (ref "U$4") (pin "CFG-1") (pinfunction "CFG-1_CFG-1") (pintype "bidirectional"))
      (node (ref "U$5") (pin "CFG-1") (pinfunction "CFG-1_CFG-1") (pintype "bidirectional"))
    )
    (net (code "77") (name "/MOSI2") (class "Default")
      (node (ref "IC4") (pin "16") (pinfunction "(PDI/MOSI/PCINT2)PB2_16") (pintype "bidirectional"))
      (node (ref "ICSP1") (pin "4") (pinfunction "4_4") (pintype "passive"))
    )
    (net (code "78") (name "/RD+") (class "Default")
      (node (ref "IC4") (pin "29") (pinfunction "D+_29") (pintype "bidirectional"))
      (node (ref "R6") (pin "1") (pinfunction "1_1") (pintype "passive"))
    )
    (net (code "79") (name "/RD-") (class "Default")
      (node (ref "IC4") (pin "30") (pinfunction "D-_30") (pintype "bidirectional"))
      (node (ref "R5") (pin "1") (pinfunction "1_1") (pintype "passive"))
    )
    (net (code "80") (name "/RESET") (class "Default")
      (node (ref "ATMEGA2560") (pin "30") (pinfunction "RESET_30") (pintype "input"))
      (node (ref "C1") (pin "1") (pinfunction "1_1") (pintype "passive"))
      (node (ref "C7") (pin "2") (pinfunction "2_2") (pintype "passive"))
      (node (ref "D3") (pin "A") (pinfunction "A_A") (pintype "passive"))
      (node (ref "ICSP") (pin "5") (pinfunction "5_5") (pintype "passive"))
      (node (ref "R4") (pin "1") (pinfunction "1_1") (pintype "passive"))
      (node (ref "RESET") (pin "3") (pinfunction "P_3") (pintype "passive"))
    )
    (net (code "81") (name "/RESET2") (class "Default")
      (node (ref "D2") (pin "A") (pinfunction "A_A") (pintype "passive"))
      (node (ref "IC4") (pin "24") (pinfunction "RESET(PC1/DW)_24") (pintype "input"))
      (node (ref "ICSP1") (pin "5") (pinfunction "5_5") (pintype "passive"))
      (node (ref "R3") (pin "1") (pinfunction "1_1") (pintype "passive"))
    )
    (net (code "82") (name "/RXL") (class "Default")
      (node (ref "IC4") (pin "10") (pinfunction "(INT5/AIN3)PD4_10") (pintype "bidirectional"))
      (node (ref "RX") (pin "C") (pinfunction "C_C") (pintype "passive"))
    )
    (net (code "83") (name "/SCK") (class "Default")
      (node (ref "ATMEGA2560") (pin "20") (pinfunction "(SCK/PCINT1)PB1_20") (pintype "bidirectional"))
      (node (ref "ICSP") (pin "3") (pinfunction "3_3") (pintype "passive"))
      (node (ref "U$1") (pin "CFG-2") (pinfunction "CFG-2_CFG-2") (pintype "bidirectional"))
      (node (ref "U$2") (pin "CFG-2") (pinfunction "CFG-2_CFG-2") (pintype "bidirectional"))
      (node (ref "U$3") (pin "CFG-2") (pinfunction "CFG-2_CFG-2") (pintype "bidirectional"))
      (node (ref "U$4") (pin "CFG-2") (pinfunction "CFG-2_CFG-2") (pintype "bidirectional"))
      (node (ref "U$5") (pin "CFG-2") (pinfunction "CFG-2_CFG-2") (pintype "bidirectional"))
    )
    (net (code "84") (name "/SCK2") (class "Default")
      (node (ref "IC4") (pin "15") (pinfunction "(SCLK/PCINT1)PB1_15") (pintype "bidirectional"))
      (node (ref "ICSP1") (pin "3") (pinfunction "3_3") (pintype "passive"))
    )
    (net (code "85") (name "/SCL") (class "Default")
      (node (ref "ATMEGA2560") (pin "43") (pinfunction "(SCL/INT0)PD0_43") (pintype "bidirectional"))
      (node (ref "I2C") (pin "4") (pinfunction "4_4") (pintype "passive"))
      (node (ref "R12") (pin "1") (pinfunction "1_1") (pintype "passive"))
    )
    (net (code "86") (name "/SDA") (class "Default")
      (node (ref "ATMEGA2560") (pin "44") (pinfunction "(SDA/INT1)PD1_44") (pintype "bidirectional"))
      (node (ref "I2C") (pin "3") (pinfunction "3_3") (pintype "passive"))
      (node (ref "R11") (pin "1") (pinfunction "1_1") (pintype "passive"))
    )
    (net (code "87") (name "/TXL") (class "Default")
      (node (ref "IC4") (pin "11") (pinfunction "(XCK/AIN4/PCINT12)PD5_11") (pintype "bidirectional"))
      (node (ref "TX") (pin "C") (pinfunction "C_C") (pintype "passive"))
    )
    (net (code "88") (name "/USBVCC") (class "Default")
      (node (ref "C8") (pin "1") (pinfunction "1_1") (pintype "passive"))
      (node (ref "F2") (pin "1") (pinfunction "1_1") (pintype "passive"))
      (node (ref "IC4") (pin "31") (pinfunction "UVCC_31") (pintype "power_in"))
    )
    (net (code "89") (name "/USHIELD") (class "Default")
      (node (ref "L1") (pin "2") (pinfunction "2_2") (pintype "passive"))
      (node (ref "X2") (pin "P$1") (pinfunction "P$1_P$1") (pintype "bidirectional"))
      (node (ref "X2") (pin "P$2") (pinfunction "P$2_P$2") (pintype "bidirectional"))
      (node (ref "Z1") (pin "1") (pinfunction "1_1") (pintype "passive"))
      (node (ref "Z2") (pin "1") (pinfunction "1_1") (pintype "passive"))
    )
    (net (code "90") (name "/VIN") (class "Default")
      (node (ref "C2") (pin "1") (pinfunction "1_1") (pintype "passive"))
      (node (ref "D4") (pin "C") (pinfunction "C_C") (pintype "passive"))
      (node (ref "IC1") (pin "3") (pinfunction "IN_3") (pintype "input"))
      (node (ref "PC1") (pin "+") (pinfunction "+_+") (pintype "passive"))
    )
    (net (code "91") (name "/VUCAP") (class "Default")
      (node (ref "C10") (pin "1") (pinfunction "1_1") (pintype "passive"))
      (node (ref "IC4") (pin "27") (pinfunction "UCAP_27") (pintype "passive"))
    )
    (net (code "92") (name "/XT1") (class "Default")
      (node (ref "C14") (pin "1") (pinfunction "1_1") (pintype "passive"))
      (node (ref "IC4") (pin "1") (pinfunction "XTAL1_1") (pintype "bidirectional"))
      (node (ref "R2") (pin "1") (pinfunction "1_1") (pintype "passive"))
      (node (ref "Y2") (pin "2") (pinfunction "2_2") (pintype "passive"))
    )
    (net (code "93") (name "/XT2") (class "Default")
      (node (ref "C15") (pin "1") (pinfunction "1_1") (pintype "passive"))
      (node (ref "IC4") (pin "2") (pinfunction "XTAL2(PC0)_2") (pintype "bidirectional"))
      (node (ref "R2") (pin "2") (pinfunction "2_2") (pintype "passive"))
      (node (ref "Y2") (pin "1") (pinfunction "1_1") (pintype "passive"))
    )
    (net (code "94") (name "/XTAL1") (class "Default")
      (node (ref "ATMEGA2560") (pin "34") (pinfunction "XTAL1_34") (pintype "input"))
      (node (ref "R1") (pin "1") (pinfunction "1_1") (pintype "passive"))
      (node (ref "Y1") (pin "3") (pinfunction "3_3") (pintype "passive"))
    )
    (net (code "95") (name "/XTAL2") (class "Default")
      (node (ref "ATMEGA2560") (pin "33") (pinfunction "XTAL2_33") (pintype "output"))
      (node (ref "R1") (pin "2") (pinfunction "2_2") (pintype "passive"))
      (node (ref "Y1") (pin "1") (pinfunction "1_1") (pintype "passive"))
    )
    (net (code "96") (name "/XVCC") (class "Default")
      (node (ref "F2") (pin "2") (pinfunction "2_2") (pintype "passive"))
      (node (ref "X2") (pin "1") (pinfunction "1_1") (pintype "bidirectional"))
    )
    (net (code "97") (name "GND") (class "Default")
      (node (ref "A-OUT") (pin "2") (pinfunction "2_2") (pintype "passive"))
      (node (ref "ATMEGA2560") (pin "11") (pinfunction "GND_11") (pintype "power_in"))
      (node (ref "ATMEGA2560") (pin "32") (pinfunction "GND1_32") (pintype "power_in"))
      (node (ref "ATMEGA2560") (pin "62") (pinfunction "GND2_62") (pintype "power_in"))
      (node (ref "ATMEGA2560") (pin "81") (pinfunction "GND3_81") (pintype "power_in"))
      (node (ref "ATMEGA2560") (pin "99") (pinfunction "AGND_99") (pintype "power_in"))
      (node (ref "AUX-4") (pin "23") (pinfunction "23_23") (pintype "passive"))
      (node (ref "AUX-4") (pin "24") (pinfunction "24_24") (pintype "passive"))
      (node (ref "AUX-4") (pin "3") (pinfunction "3_3") (pintype "passive"))
      (node (ref "AUX-4") (pin "4") (pinfunction "4_4") (pintype "passive"))
      (node (ref "C1") (pin "2") (pinfunction "2_2") (pintype "passive"))
      (node (ref "C10") (pin "2") (pinfunction "2_2") (pintype "passive"))
      (node (ref "C11") (pin "2") (pinfunction "2_2") (pintype "passive"))
      (node (ref "C12") (pin "-") (pinfunction "-_-") (pintype "passive"))
      (node (ref "C13") (pin "2") (pinfunction "2_2") (pintype "passive"))
      (node (ref "C14") (pin "2") (pinfunction "2_2") (pintype "passive"))
      (node (ref "C15") (pin "2") (pinfunction "2_2") (pintype "passive"))
      (node (ref "C2") (pin "2") (pinfunction "2_2") (pintype "passive"))
      (node (ref "C21") (pin "-") (pinfunction "-_-") (pintype "passive"))
      (node (ref "C22") (pin "-") (pinfunction "-_-") (pintype "passive"))
      (node (ref "C23") (pin "-") (pinfunction "-_-") (pintype "passive"))
      (node (ref "C24") (pin "-") (pinfunction "-_-") (pintype "passive"))
      (node (ref "C25") (pin "-") (pinfunction "-_-") (pintype "passive"))
      (node (ref "C4") (pin "2") (pinfunction "2_2") (pintype "passive"))
      (node (ref "C40") (pin "-") (pinfunction "-_-") (pintype "passive"))
      (node (ref "C41") (pin "-") (pinfunction "-_-") (pintype "passive"))
      (node (ref "C42") (pin "-") (pinfunction "-_-") (pintype "passive"))
      (node (ref "C43") (pin "-") (pinfunction "-_-") (pintype "passive"))
      (node (ref "C5") (pin "2") (pinfunction "2_2") (pintype "passive"))
      (node (ref "C6") (pin "2") (pinfunction "2_2") (pintype "passive"))
      (node (ref "C8") (pin "2") (pinfunction "2_2") (pintype "passive"))
      (node (ref "C9") (pin "2") (pinfunction "2_2") (pintype "passive"))
      (node (ref "D5") (pin "A") (pinfunction "A_A") (pintype "passive"))
      (node (ref "I2C") (pin "2") (pinfunction "2_2") (pintype "passive"))
      (node (ref "IC1") (pin "1") (pinfunction "GND/ADJ_1") (pintype "input"))
      (node (ref "IC4") (pin "28") (pinfunction "UGND_28") (pintype "power_in"))
      (node (ref "IC4") (pin "3") (pinfunction "GND_3") (pintype "power_in"))
      (node (ref "IC4") (pin "33") (pinfunction "PAD_33") (pintype "power_in"))
      (node (ref "ICSP") (pin "6") (pinfunction "6_6") (pintype "passive"))
      (node (ref "ICSP1") (pin "6") (pinfunction "6_6") (pintype "passive"))
      (node (ref "J1") (pin "2") (pinfunction "2_2") (pintype "passive"))
      (node (ref "J2") (pin "1") (pinfunction "1_1") (pintype "passive"))
      (node (ref "J3") (pin "1") (pinfunction "1_1") (pintype "passive"))
      (node (ref "J4") (pin "1") (pinfunction "1_1") (pintype "passive"))
      (node (ref "J5") (pin "1") (pinfunction "1_1") (pintype "passive"))
      (node (ref "JP7") (pin "1") (pinfunction "1_1") (pintype "passive"))
      (node (ref "JP7") (pin "3") (pinfunction "3_3") (pintype "passive"))
      (node (ref "JP7") (pin "5") (pinfunction "5_5") (pintype "passive"))
      (node (ref "JP7") (pin "7") (pinfunction "7_7") (pintype "passive"))
      (node (ref "L") (pin "C") (pinfunction "C_C") (pintype "passive"))
      (node (ref "L1") (pin "1") (pinfunction "1_1") (pintype "passive"))
      (node (ref "ON") (pin "C") (pinfunction "C_C") (pintype "passive"))
      (node (ref "P1") (pin "3") (pinfunction "CW_3") (pintype "bidirectional"))
      (node (ref "PC1") (pin "-") (pinfunction "-_-") (pintype "passive"))
      (node (ref "PC2") (pin "-") (pinfunction "-_-") (pintype "passive"))
      (node (ref "Q1") (pin "S") (pinfunction "S_S") (pintype "passive"))
      (node (ref "Q2") (pin "S") (pinfunction "S_S") (pintype "passive"))
      (node (ref "Q3") (pin "1") (pinfunction "S_1") (pintype "passive"))
      (node (ref "Q3") (pin "3") (pinfunction "S_3") (pintype "passive"))
      (node (ref "Q4") (pin "1") (pinfunction "S_1") (pintype "passive"))
      (node (ref "Q4") (pin "3") (pinfunction "S_3") (pintype "passive"))
      (node (ref "R13") (pin "1") (pinfunction "1_1") (pintype "passive"))
      (node (ref "R62") (pin "2") (pinfunction "2_2") (pintype "passive"))
      (node (ref "R63") (pin "2") (pinfunction "2_2") (pintype "passive"))
      (node (ref "R66") (pin "2") (pinfunction "2_2") (pintype "passive"))
      (node (ref "R67") (pin "2") (pinfunction "2_2") (pintype "passive"))
      (node (ref "R68") (pin "2") (pinfunction "2_2") (pintype "passive"))
      (node (ref "R69") (pin "2") (pinfunction "2_2") (pintype "passive"))
      (node (ref "RESET") (pin "1") (pinfunction "S_1") (pintype "passive"))
      (node (ref "RN4") (pin "5") (pinfunction "2_5") (pintype "passive"))
      (node (ref "SERIAL") (pin "2") (pinfunction "2_2") (pintype "passive"))
      (node (ref "U$1") (pin "GND") (pinfunction "GND_GND") (pintype "power_in"))
      (node (ref "U$1") (pin "GND@0") (pinfunction "GND_GND@0") (pintype "power_in"))
      (node (ref "U$2") (pin "GND") (pinfunction "GND_GND") (pintype "power_in"))
      (node (ref "U$2") (pin "GND@0") (pinfunction "GND_GND@0") (pintype "power_in"))
      (node (ref "U$3") (pin "GND") (pinfunction "GND_GND") (pintype "power_in"))
      (node (ref "U$3") (pin "GND@0") (pinfunction "GND_GND@0") (pintype "power_in"))
      (node (ref "U$4") (pin "GND") (pinfunction "GND_GND") (pintype "power_in"))
      (node (ref "U$4") (pin "GND@0") (pinfunction "GND_GND@0") (pintype "power_in"))
      (node (ref "U$5") (pin "GND") (pinfunction "GND_GND") (pintype "power_in"))
      (node (ref "U$5") (pin "GND@0") (pinfunction "GND_GND@0") (pintype "power_in"))
      (node (ref "X+") (pin "2") (pinfunction "2_2") (pintype "passive"))
      (node (ref "X-") (pin "2") (pinfunction "2_2") (pintype "passive"))
      (node (ref "X1") (pin "2") (pinfunction "1_2") (pintype "passive"))
      (node (ref "X2") (pin "4") (pinfunction "4_4") (pintype "bidirectional"))
      (node (ref "Y+") (pin "2") (pinfunction "2_2") (pintype "passive"))
      (node (ref "Y-") (pin "2") (pinfunction "2_2") (pintype "passive"))
      (node (ref "Y1") (pin "2") (pinfunction "2_2") (pintype "passive"))
      (node (ref "Z+") (pin "2") (pinfunction "2_2") (pintype "passive"))
      (node (ref "Z-") (pin "2") (pinfunction "2_2") (pintype "passive"))
      (node (ref "Z12V") (pin "2") (pinfunction "2_2") (pintype "passive"))
    )
    (net (code "98") (name "Net-(F1-Pad2)") (class "Default")
      (node (ref "F1") (pin "2") (pinfunction "2_2") (pintype "passive"))
      (node (ref "X1") (pin "1") (pinfunction "1_1") (pintype "passive"))
    )
    (net (code "99") (name "Net-(FANS-Pad2)") (class "Default")
      (node (ref "FANS") (pin "2") (pinfunction "2_2") (pintype "passive"))
      (node (ref "L6") (pin "C") (pinfunction "C_C") (pintype "passive"))
      (node (ref "Q3") (pin "5") (pinfunction "D_5") (pintype "passive"))
      (node (ref "Q3") (pin "6") (pinfunction "D_6") (pintype "passive"))
    )
    (net (code "100") (name "Net-(FANS-Pad4)") (class "Default")
      (node (ref "FANS") (pin "4") (pinfunction "4_4") (pintype "passive"))
      (node (ref "L7") (pin "C") (pinfunction "C_C") (pintype "passive"))
      (node (ref "Q3") (pin "7") (pinfunction "D_7") (pintype "passive"))
      (node (ref "Q3") (pin "8") (pinfunction "D_8") (pintype "passive"))
    )
    (net (code "101") (name "Net-(FANS-Pad6)") (class "Default")
      (node (ref "FANS") (pin "6") (pinfunction "6_6") (pintype "passive"))
      (node (ref "L8") (pin "C") (pinfunction "C_C") (pintype "passive"))
      (node (ref "Q4") (pin "5") (pinfunction "D_5") (pintype "passive"))
      (node (ref "Q4") (pin "6") (pinfunction "D_6") (pintype "passive"))
    )
    (net (code "102") (name "Net-(FANS-Pad8)") (class "Default")
      (node (ref "FANS") (pin "8") (pinfunction "8_8") (pintype "passive"))
      (node (ref "LED6") (pin "C") (pinfunction "C_C") (pintype "passive"))
      (node (ref "Q4") (pin "7") (pinfunction "D_7") (pintype "passive"))
      (node (ref "Q4") (pin "8") (pinfunction "D_8") (pintype "passive"))
    )
    (net (code "103") (name "Net-(L-PadA)") (class "Default")
      (node (ref "L") (pin "A") (pinfunction "A_A") (pintype "passive"))
      (node (ref "RN3") (pin "1") (pinfunction "1_1") (pintype "passive"))
    )
    (net (code "104") (name "Net-(L6-PadA)") (class "Default")
      (node (ref "L6") (pin "A") (pinfunction "A_A") (pintype "passive"))
      (node (ref "R76") (pin "1") (pinfunction "1_1") (pintype "passive"))
    )
    (net (code "105") (name "Net-(L7-PadA)") (class "Default")
      (node (ref "L7") (pin "A") (pinfunction "A_A") (pintype "passive"))
      (node (ref "R77") (pin "1") (pinfunction "1_1") (pintype "passive"))
    )
    (net (code "106") (name "Net-(L8-PadA)") (class "Default")
      (node (ref "L8") (pin "A") (pinfunction "A_A") (pintype "passive"))
      (node (ref "R78") (pin "1") (pinfunction "1_1") (pintype "passive"))
    )
    (net (code "107") (name "Net-(LED1-PadA)") (class "Default")
      (node (ref "LED1") (pin "A") (pinfunction "A_A") (pintype "passive"))
      (node (ref "R72") (pin "2") (pinfunction "2_2") (pintype "passive"))
    )
    (net (code "108") (name "Net-(LED1-PadC)") (class "Default")
      (node (ref "LED1") (pin "C") (pinfunction "C_C") (pintype "passive"))
      (node (ref "Q1") (pin "D") (pinfunction "D_D") (pintype "passive"))
      (node (ref "X3") (pin "1") (pinfunction "1_1") (pintype "passive"))
    )
    (net (code "109") (name "Net-(LED2-PadA)") (class "Default")
      (node (ref "LED2") (pin "A") (pinfunction "A_A") (pintype "passive"))
      (node (ref "R73") (pin "2") (pinfunction "2_2") (pintype "passive"))
    )
    (net (code "110") (name "Net-(LED6-PadA)") (class "Default")
      (node (ref "LED6") (pin "A") (pinfunction "A_A") (pintype "passive"))
      (node (ref "R79") (pin "1") (pinfunction "1_1") (pintype "passive"))
    )
    (net (code "111") (name "Net-(Q1-PadG)") (class "Default")
      (node (ref "Q1") (pin "G") (pinfunction "G_G") (pintype "passive"))
      (node (ref "R52") (pin "2") (pinfunction "2_2") (pintype "passive"))
    )
    (net (code "112") (name "Net-(Q2-PadG)") (class "Default")
      (node (ref "Q2") (pin "G") (pinfunction "G_G") (pintype "passive"))
      (node (ref "R53") (pin "2") (pinfunction "2_2") (pintype "passive"))
    )
    (net (code "113") (name "Net-(Q3A-G)") (class "Default")
      (node (ref "Q3") (pin "2") (pinfunction "G_2") (pintype "passive"))
      (node (ref "R57") (pin "2") (pinfunction "2_2") (pintype "passive"))
    )
    (net (code "114") (name "Net-(Q3B-G)") (class "Default")
      (node (ref "Q3") (pin "4") (pinfunction "G_4") (pintype "passive"))
      (node (ref "R56") (pin "2") (pinfunction "2_2") (pintype "passive"))
    )
    (net (code "115") (name "Net-(Q4A-G)") (class "Default")
      (node (ref "Q4") (pin "2") (pinfunction "G_2") (pintype "passive"))
      (node (ref "R59") (pin "2") (pinfunction "2_2") (pintype "passive"))
    )
    (net (code "116") (name "Net-(Q4B-G)") (class "Default")
      (node (ref "Q4") (pin "4") (pinfunction "G_4") (pintype "passive"))
      (node (ref "R58") (pin "2") (pinfunction "2_2") (pintype "passive"))
    )
    (net (code "117") (name "Net-(RN3B-2)") (class "Default")
      (node (ref "ON") (pin "A") (pinfunction "A_A") (pintype "passive"))
      (node (ref "RN3") (pin "7") (pinfunction "2_7") (pintype "passive"))
    )
    (net (code "118") (name "Net-(RN3C-2)") (class "Default")
      (node (ref "RN3") (pin "6") (pinfunction "2_6") (pintype "passive"))
      (node (ref "RX") (pin "A") (pinfunction "A_A") (pintype "passive"))
    )
    (net (code "119") (name "Net-(RN3D-2)") (class "Default")
      (node (ref "RN3") (pin "5") (pinfunction "2_5") (pintype "passive"))
      (node (ref "TX") (pin "A") (pinfunction "A_A") (pintype "passive"))
    )
    (net (code "120") (name "Net-(U$1-O1A)") (class "Default")
      (node (ref "U$1") (pin "OA1") (pinfunction "O1A_OA1") (pintype "output"))
      (node (ref "X-MOT") (pin "3") (pinfunction "3_3") (pintype "passive"))
    )
    (net (code "121") (name "Net-(U$1-O1B)") (class "Default")
      (node (ref "U$1") (pin "OA2") (pinfunction "O1B_OA2") (pintype "output"))
      (node (ref "X-MOT") (pin "4") (pinfunction "4_4") (pintype "passive"))
    )
    (net (code "122") (name "Net-(U$1-O2A)") (class "Default")
      (node (ref "U$1") (pin "OB1") (pinfunction "O2A_OB1") (pintype "output"))
      (node (ref "X-MOT") (pin "2") (pinfunction "2_2") (pintype "passive"))
    )
    (net (code "123") (name "Net-(U$1-O2B)") (class "Default")
      (node (ref "U$1") (pin "OB2") (pinfunction "O2B_OB2") (pintype "output"))
      (node (ref "X-MOT") (pin "1") (pinfunction "1_1") (pintype "passive"))
    )
    (net (code "124") (name "Net-(U$2-O1A)") (class "Default")
      (node (ref "U$2") (pin "OA1") (pinfunction "O1A_OA1") (pintype "output"))
      (node (ref "Y-MOT") (pin "3") (pinfunction "3_3") (pintype "passive"))
    )
    (net (code "125") (name "Net-(U$2-O1B)") (class "Default")
      (node (ref "U$2") (pin "OA2") (pinfunction "O1B_OA2") (pintype "output"))
      (node (ref "Y-MOT") (pin "4") (pinfunction "4_4") (pintype "passive"))
    )
    (net (code "126") (name "Net-(U$2-O2A)") (class "Default")
      (node (ref "U$2") (pin "OB1") (pinfunction "O2A_OB1") (pintype "output"))
      (node (ref "Y-MOT") (pin "2") (pinfunction "2_2") (pintype "passive"))
    )
    (net (code "127") (name "Net-(U$2-O2B)") (class "Default")
      (node (ref "U$2") (pin "OB2") (pinfunction "O2B_OB2") (pintype "output"))
      (node (ref "Y-MOT") (pin "1") (pinfunction "1_1") (pintype "passive"))
    )
    (net (code "128") (name "Net-(U$3-O1A)") (class "Default")
      (node (ref "U$3") (pin "OA1") (pinfunction "O1A_OA1") (pintype "output"))
      (node (ref "Z-MOT") (pin "3") (pinfunction "3_3") (pintype "passive"))
      (node (ref "Z-MOT1") (pin "3") (pinfunction "3_3") (pintype "passive"))
    )
    (net (code "129") (name "Net-(U$3-O1B)") (class "Default")
      (node (ref "U$3") (pin "OA2") (pinfunction "O1B_OA2") (pintype "output"))
      (node (ref "Z-MOT") (pin "4") (pinfunction "4_4") (pintype "passive"))
      (node (ref "Z-MOT1") (pin "4") (pinfunction "4_4") (pintype "passive"))
    )
    (net (code "130") (name "Net-(U$3-O2A)") (class "Default")
      (node (ref "U$3") (pin "OB1") (pinfunction "O2A_OB1") (pintype "output"))
      (node (ref "Z-MOT") (pin "2") (pinfunction "2_2") (pintype "passive"))
      (node (ref "Z-MOT1") (pin "2") (pinfunction "2_2") (pintype "passive"))
    )
    (net (code "131") (name "Net-(U$3-O2B)") (class "Default")
      (node (ref "U$3") (pin "OB2") (pinfunction "O2B_OB2") (pintype "output"))
      (node (ref "Z-MOT") (pin "1") (pinfunction "1_1") (pintype "passive"))
      (node (ref "Z-MOT1") (pin "1") (pinfunction "1_1") (pintype "passive"))
    )
    (net (code "132") (name "Net-(U$4-O1A)") (class "Default")
      (node (ref "E1-MOT") (pin "3") (pinfunction "3_3") (pintype "passive"))
      (node (ref "U$4") (pin "OA1") (pinfunction "O1A_OA1") (pintype "output"))
    )
    (net (code "133") (name "Net-(U$4-O1B)") (class "Default")
      (node (ref "E1-MOT") (pin "4") (pinfunction "4_4") (pintype "passive"))
      (node (ref "U$4") (pin "OA2") (pinfunction "O1B_OA2") (pintype "output"))
    )
    (net (code "134") (name "Net-(U$4-O2A)") (class "Default")
      (node (ref "E1-MOT") (pin "2") (pinfunction "2_2") (pintype "passive"))
      (node (ref "U$4") (pin "OB1") (pinfunction "O2A_OB1") (pintype "output"))
    )
    (net (code "135") (name "Net-(U$4-O2B)") (class "Default")
      (node (ref "E1-MOT") (pin "1") (pinfunction "1_1") (pintype "passive"))
      (node (ref "U$4") (pin "OB2") (pinfunction "O2B_OB2") (pintype "output"))
    )
    (net (code "136") (name "Net-(U$5-O1A)") (class "Default")
      (node (ref "E0-MOT") (pin "3") (pinfunction "3_3") (pintype "passive"))
      (node (ref "U$5") (pin "OA1") (pinfunction "O1A_OA1") (pintype "output"))
    )
    (net (code "137") (name "Net-(U$5-O1B)") (class "Default")
      (node (ref "E0-MOT") (pin "4") (pinfunction "4_4") (pintype "passive"))
      (node (ref "U$5") (pin "OA2") (pinfunction "O1B_OA2") (pintype "output"))
    )
    (net (code "138") (name "Net-(U$5-O2A)") (class "Default")
      (node (ref "E0-MOT") (pin "2") (pinfunction "2_2") (pintype "passive"))
      (node (ref "U$5") (pin "OB1") (pinfunction "O2A_OB1") (pintype "output"))
    )
    (net (code "139") (name "Net-(U$5-O2B)") (class "Default")
      (node (ref "E0-MOT") (pin "1") (pinfunction "1_1") (pintype "passive"))
      (node (ref "U$5") (pin "OB2") (pinfunction "O2B_OB2") (pintype "output"))
    )
    (net (code "140") (name "Net-(X3C-1)") (class "Default")
      (node (ref "LED2") (pin "C") (pinfunction "C_C") (pintype "passive"))
      (node (ref "Q2") (pin "D") (pinfunction "D_D") (pintype "passive"))
      (node (ref "X3") (pin "3") (pinfunction "1_3") (pintype "passive"))
    )
    (net (code "141") (name "unconnected-(ATMEGA2560-(CLKO{slash}ICP3{slash}INT7)PE7-Pad9)") (class "Default")
      (node (ref "ATMEGA2560") (pin "9") (pinfunction "(CLKO/ICP3/INT7)PE7_9") (pintype "bidirectional"))
    )
    (net (code "142") (name "unconnected-(ATMEGA2560-(ICP1)PD4-Pad47)") (class "Default")
      (node (ref "ATMEGA2560") (pin "47") (pinfunction "(ICP1)PD4_47") (pintype "bidirectional"))
    )
    (net (code "143") (name "unconnected-(ATMEGA2560-(T1)PD6-Pad49)") (class "Default")
      (node (ref "ATMEGA2560") (pin "49") (pinfunction "(T1)PD6_49") (pintype "bidirectional"))
    )
    (net (code "144") (name "unconnected-(ATMEGA2560-(T3{slash}INT6)PE6-Pad8)") (class "Default")
      (node (ref "ATMEGA2560") (pin "8") (pinfunction "(T3/INT6)PE6_8") (pintype "bidirectional"))
    )
    (net (code "145") (name "unconnected-(ATMEGA2560-(TOSC1)PG4-Pad29)") (class "Default")
      (node (ref "ATMEGA2560") (pin "29") (pinfunction "(TOSC1)PG4_29") (pintype "bidirectional"))
    )
    (net (code "146") (name "unconnected-(ATMEGA2560-(TOSC2)PG3-Pad28)") (class "Default")
      (node (ref "ATMEGA2560") (pin "28") (pinfunction "(TOSC2)PG3_28") (pintype "bidirectional"))
    )
    (net (code "147") (name "unconnected-(ATMEGA2560-(XCK0{slash}AIN0)PE2-Pad4)") (class "Default")
      (node (ref "ATMEGA2560") (pin "4") (pinfunction "(XCK0/AIN0)PE2_4") (pintype "bidirectional"))
    )
    (net (code "148") (name "unconnected-(ATMEGA2560-(XCK1)PD5-Pad48)") (class "Default")
      (node (ref "ATMEGA2560") (pin "48") (pinfunction "(XCK1)PD5_48") (pintype "bidirectional"))
    )
    (net (code "149") (name "unconnected-(ATMEGA2560-AREF-Pad98)") (class "Default")
      (node (ref "ATMEGA2560") (pin "98") (pinfunction "AREF_98") (pintype "bidirectional"))
    )
    (net (code "150") (name "unconnected-(ATMEGA2560-PH2(XCK2)-Pad14)") (class "Default")
      (node (ref "ATMEGA2560") (pin "14") (pinfunction "PH2(XCK2)_14") (pintype "bidirectional"))
    )
    (net (code "151") (name "unconnected-(ATMEGA2560-PH7(T4)-Pad27)") (class "Default")
      (node (ref "ATMEGA2560") (pin "27") (pinfunction "PH7(T4)_27") (pintype "bidirectional"))
    )
    (net (code "152") (name "unconnected-(ATMEGA2560-PJ2(XCK3{slash}PCINT11)-Pad65)") (class "Default")
      (node (ref "ATMEGA2560") (pin "65") (pinfunction "PJ2(XCK3/PCINT11)_65") (pintype "bidirectional"))
    )
    (net (code "153") (name "unconnected-(ATMEGA2560-PJ3(PCINT12)-Pad66)") (class "Default")
      (node (ref "ATMEGA2560") (pin "66") (pinfunction "PJ3(PCINT12)_66") (pintype "bidirectional"))
    )
    (net (code "154") (name "unconnected-(ATMEGA2560-PJ4(PCINT13)-Pad67)") (class "Default")
      (node (ref "ATMEGA2560") (pin "67") (pinfunction "PJ4(PCINT13)_67") (pintype "bidirectional"))
    )
    (net (code "155") (name "unconnected-(ATMEGA2560-PJ5(PCINT14)-Pad68)") (class "Default")
      (node (ref "ATMEGA2560") (pin "68") (pinfunction "PJ5(PCINT14)_68") (pintype "bidirectional"))
    )
    (net (code "156") (name "unconnected-(ATMEGA2560-PJ6(PCINT15)-Pad69)") (class "Default")
      (node (ref "ATMEGA2560") (pin "69") (pinfunction "PJ6(PCINT15)_69") (pintype "bidirectional"))
    )
    (net (code "157") (name "unconnected-(ATMEGA2560-PJ7-Pad79)") (class "Default")
      (node (ref "ATMEGA2560") (pin "79") (pinfunction "PJ7_79") (pintype "bidirectional"))
    )
    (net (code "158") (name "unconnected-(IC4-(AIN0{slash}INT1)PD1-Pad7)") (class "Default")
      (node (ref "IC4") (pin "7") (pinfunction "(AIN0/INT1)PD1_7") (pintype "bidirectional"))
    )
    (net (code "159") (name "unconnected-(IC4-(AIN2{slash}PCINT11)PC2-Pad5)") (class "Default")
      (node (ref "IC4") (pin "5") (pinfunction "(AIN2/PCINT11)PC2_5") (pintype "bidirectional"))
    )
    (net (code "160") (name "unconnected-(IC4-(INT4{slash}ICP1{slash}CLK0)PC7-Pad22)") (class "Default")
      (node (ref "IC4") (pin "22") (pinfunction "(INT4/ICP1/CLK0)PC7_22") (pintype "bidirectional"))
    )
    (net (code "161") (name "unconnected-(IC4-(OC0B{slash}INT0)PD0-Pad6)") (class "Default")
      (node (ref "IC4") (pin "6") (pinfunction "(OC0B/INT0)PD0_6") (pintype "bidirectional"))
    )
    (net (code "162") (name "unconnected-(IC4-(OC1A{slash}PCINT8)PC6-Pad23)") (class "Default")
      (node (ref "IC4") (pin "23") (pinfunction "(OC1A/PCINT8)PC6_23") (pintype "bidirectional"))
    )
    (net (code "163") (name "unconnected-(IC4-(PCINT5)PB5-Pad19)") (class "Default")
      (node (ref "IC4") (pin "19") (pinfunction "(PCINT5)PB5_19") (pintype "bidirectional"))
    )
    (net (code "164") (name "unconnected-(IC4-(PCINT6)PB6-Pad20)") (class "Default")
      (node (ref "IC4") (pin "20") (pinfunction "(PCINT6)PB6_20") (pintype "bidirectional"))
    )
    (net (code "165") (name "unconnected-(IC4-(PCINT7{slash}OC0A{slash}OC1C)PB7-Pad21)") (class "Default")
      (node (ref "IC4") (pin "21") (pinfunction "(PCINT7/OC0A/OC1C)PB7_21") (pintype "bidirectional"))
    )
    (net (code "166") (name "unconnected-(IC4-(PCINT9{slash}OC1B)PC5-Pad25)") (class "Default")
      (node (ref "IC4") (pin "25") (pinfunction "(PCINT9/OC1B)PC5_25") (pintype "bidirectional"))
    )
    (net (code "167") (name "unconnected-(IC4-(PCINT10)PC4-Pad26)") (class "Default")
      (node (ref "IC4") (pin "26") (pinfunction "(PCINT10)PC4_26") (pintype "bidirectional"))
    )
    (net (code "168") (name "unconnected-(IC4-(RTS{slash}AIN5{slash}INT6)PD6-Pad12)") (class "Default")
      (node (ref "IC4") (pin "12") (pinfunction "(RTS/AIN5/INT6)PD6_12") (pintype "bidirectional"))
    )
    (net (code "169") (name "unconnected-(IC4-(SS{slash}PCINT0)PB0-Pad14)") (class "Default")
      (node (ref "IC4") (pin "14") (pinfunction "(SS/PCINT0)PB0_14") (pintype "bidirectional"))
    )
    (net (code "170") (name "unconnected-(IC4-(T1{slash}PCINT4)PB4-Pad18)") (class "Default")
      (node (ref "IC4") (pin "18") (pinfunction "(T1/PCINT4)PB4_18") (pintype "bidirectional"))
    )
    (net (code "171") (name "unconnected-(RESET-P1-Pad4)") (class "Default")
      (node (ref "RESET") (pin "4") (pinfunction "P1_4") (pintype "passive"))
    )
    (net (code "172") (name "unconnected-(RESET-S1-Pad2)") (class "Default")
      (node (ref "RESET") (pin "2") (pinfunction "S1_2") (pintype "passive"))
    )
    (net (code "173") (name "unconnected-(RN4C-1-Pad3)") (class "Default")
      (node (ref "RN4") (pin "3") (pinfunction "1_3") (pintype "passive"))
    )
    (net (code "174") (name "unconnected-(RN4C-2-Pad6)") (class "Default")
      (node (ref "RN4") (pin "6") (pinfunction "2_6") (pintype "passive"))
    )
    (net (code "175") (name "unconnected-(U$4-PadIREF)") (class "Default")
      (node (ref "U$4") (pin "IREF") (pinfunction "IREF_IREF") (pintype "bidirectional"))
    )
    (net (code "176") (name "unconnected-(U$5-PadIREF)") (class "Default")
      (node (ref "U$5") (pin "IREF") (pinfunction "IREF_IREF") (pintype "bidirectional"))
    )
  )
)
